# lia.net
KiCad netlist of a schematic drawn in EAGLE
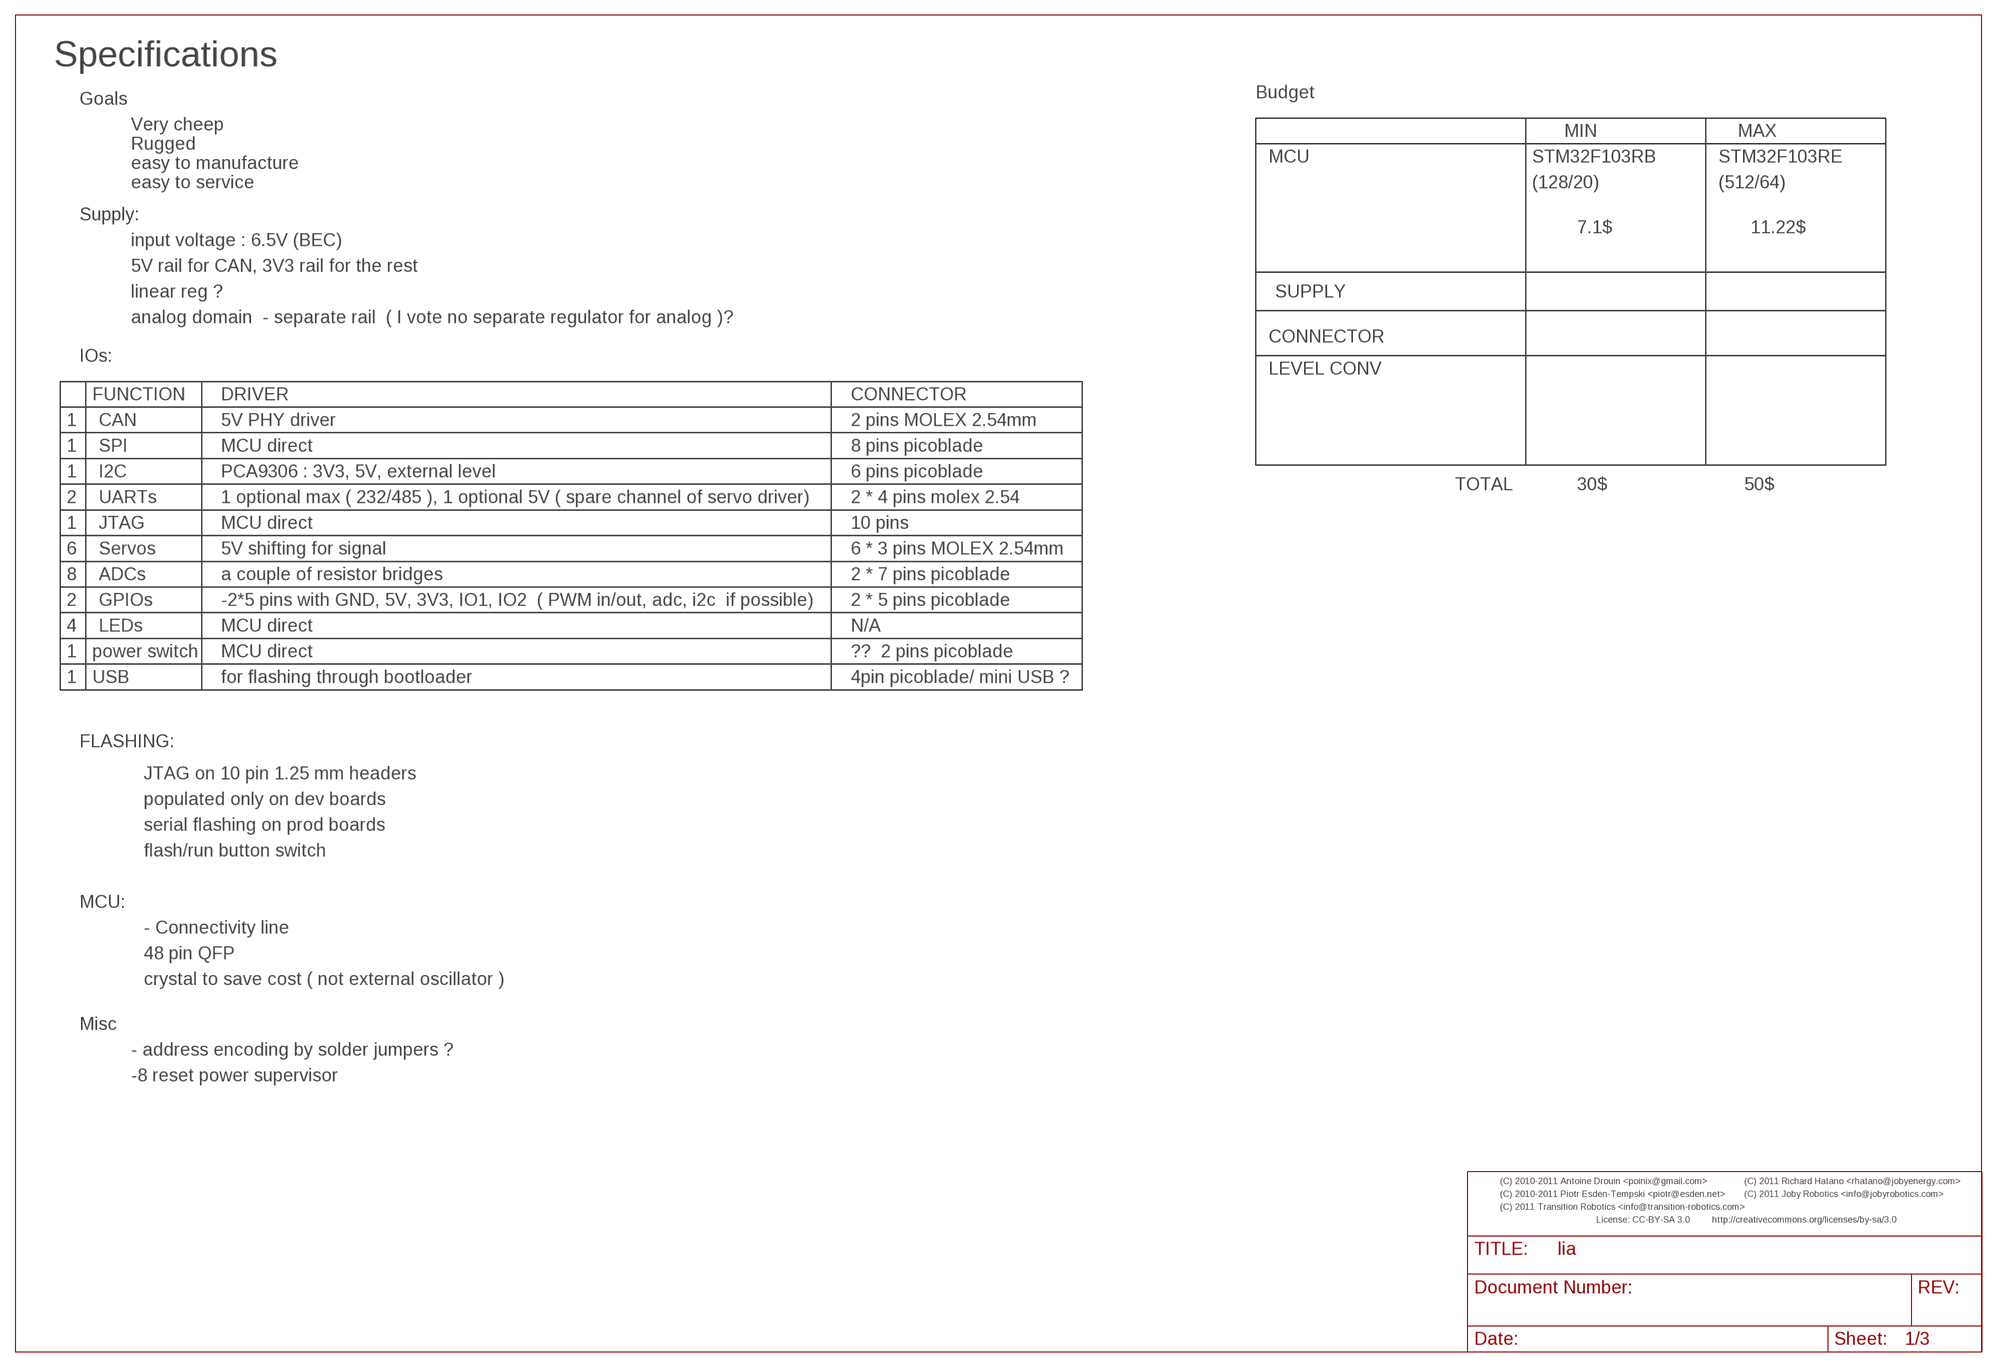
[diagram p0: schematic, sheet 1]
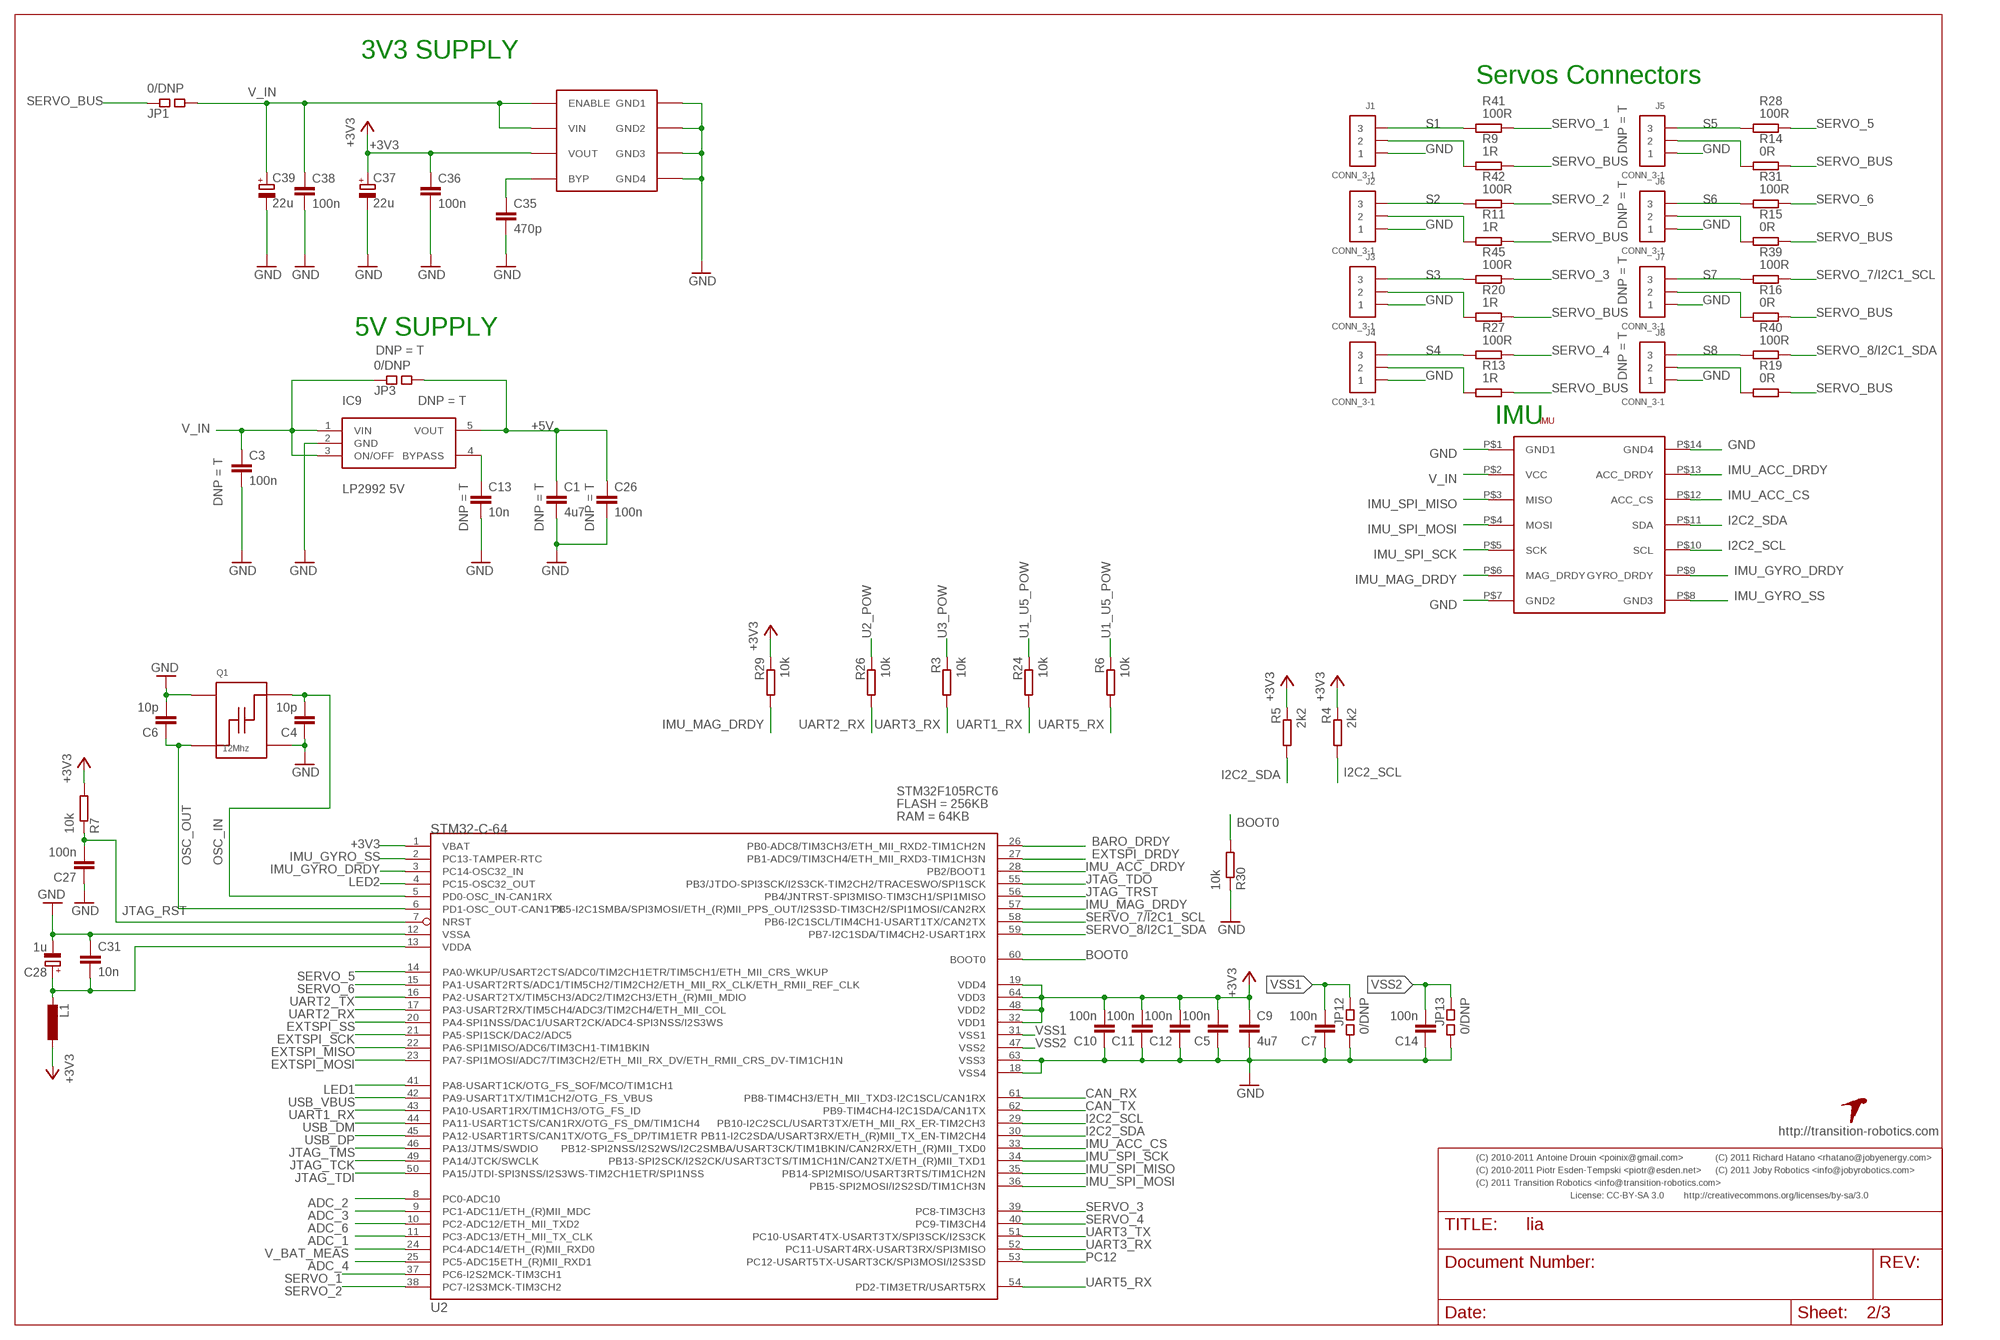
[diagram p1: schematic, sheet 2]
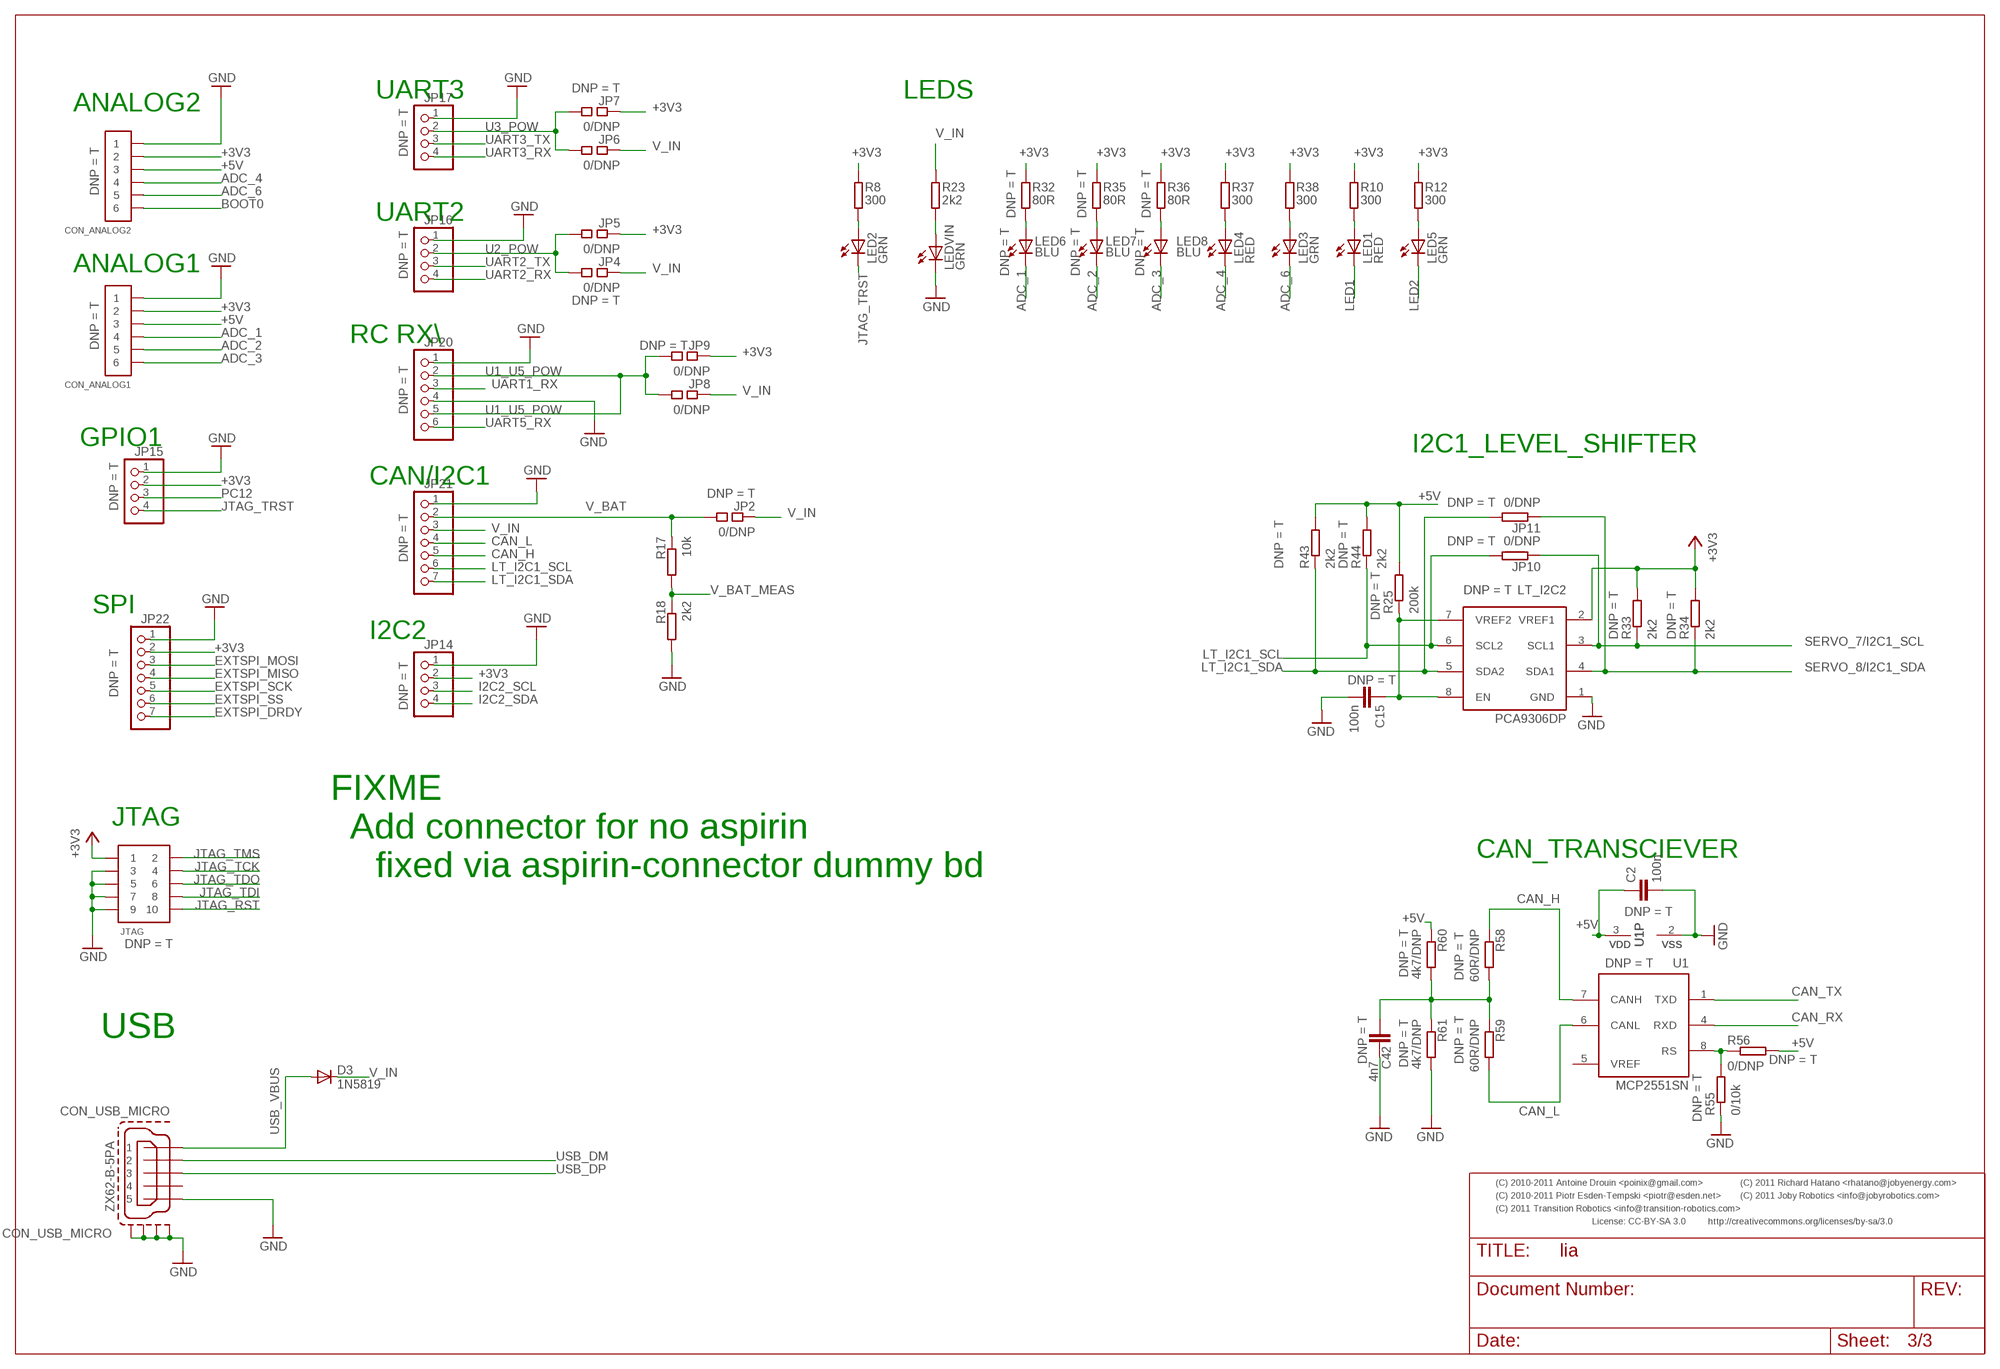
[diagram p2: schematic, sheet 3]

(export (version "E")
  (design (tool "Eeschema 10.0.6"))
  (components
    (comp (ref "C1")
      (value "4u7")
      (footprint "eagle-import:0805-CAP")
      (fields (field (name "DNP") "T") (field (name "PARTNO") "cap-cer-0805-4u7"))
      (libsource (lib "eagle-import") (part "CAPACITOR-0805"))
    )
    (comp (ref "C3")
      (value "100n")
      (footprint "eagle-import:0603-CAP")
      (fields (field (name "DNP") "T") (field (name "PARTNO") "cap-cer-0603-100n"))
      (libsource (lib "eagle-import") (part "CAPACITOR-0603"))
    )
    (comp (ref "C4")
      (value "10p")
      (footprint "eagle-import:0402-CAP")
      (fields (field (name "PARTNO") "cap-cer-0402-10p"))
      (libsource (lib "eagle-import") (part "CAPACITOR-0402"))
    )
    (comp (ref "C5")
      (value "100n")
      (footprint "eagle-import:0402-CAP")
      (fields (field (name "PARTNO") "cap-cer-0402-100n"))
      (libsource (lib "eagle-import") (part "CAPACITOR-0402"))
    )
    (comp (ref "C6")
      (value "10p")
      (footprint "eagle-import:0402-CAP")
      (fields (field (name "PARTNO") "cap-cer-0402-10p"))
      (libsource (lib "eagle-import") (part "CAPACITOR-0402"))
    )
    (comp (ref "C7")
      (value "100n")
      (footprint "eagle-import:0402-CAP")
      (fields (field (name "PARTNO") "cap-cer-0402-100n"))
      (libsource (lib "eagle-import") (part "CAPACITOR-0402"))
    )
    (comp (ref "C9")
      (value "4u7")
      (footprint "eagle-import:0805-CAP")
      (fields (field (name "PARTNO") "cap-cer-0805-4u7"))
      (libsource (lib "eagle-import") (part "CAPACITOR-0805"))
    )
    (comp (ref "C10")
      (value "100n")
      (footprint "eagle-import:0402-CAP")
      (fields (field (name "PARTNO") "cap-cer-0402-100n"))
      (libsource (lib "eagle-import") (part "CAPACITOR-0402"))
    )
    (comp (ref "C11")
      (value "100n")
      (footprint "eagle-import:0402-CAP")
      (fields (field (name "PARTNO") "cap-cer-0402-100n"))
      (libsource (lib "eagle-import") (part "CAPACITOR-0402"))
    )
    (comp (ref "C12")
      (value "100n")
      (footprint "eagle-import:0402-CAP")
      (fields (field (name "PARTNO") "cap-cer-0402-100n"))
      (libsource (lib "eagle-import") (part "CAPACITOR-0402"))
    )
    (comp (ref "C13")
      (value "10n")
      (footprint "eagle-import:0402-CAP")
      (fields (field (name "DNP") "T") (field (name "PARTNO") "cap-cer-0402-10n"))
      (libsource (lib "eagle-import") (part "CAPACITOR-0402"))
    )
    (comp (ref "C14")
      (value "100n")
      (footprint "eagle-import:0402-CAP")
      (fields (field (name "PARTNO") "cap-cer-0402-100n"))
      (libsource (lib "eagle-import") (part "CAPACITOR-0402"))
    )
    (comp (ref "C26")
      (value "100n")
      (footprint "eagle-import:0603-CAP")
      (fields (field (name "DNP") "T") (field (name "PARTNO") "cap-cer-0603-100n"))
      (libsource (lib "eagle-import") (part "CAPACITOR-0603"))
    )
    (comp (ref "C27")
      (value "100n")
      (footprint "eagle-import:0402-CAP")
      (fields (field (name "PARTNO") "cap-cer-0402-100n"))
      (libsource (lib "eagle-import") (part "CAPACITOR-0402"))
    )
    (comp (ref "C28")
      (value "1u")
      (footprint "eagle-import:0603-POL-CAP")
      (fields (field (name "PARTNO") "cap-tan-0603-1u"))
      (libsource (lib "eagle-import") (part "CAPACITOR-POL-0603"))
    )
    (comp (ref "C31")
      (value "10n")
      (footprint "eagle-import:0402-CAP")
      (fields (field (name "PARTNO") "cap-cer-0402-10n"))
      (libsource (lib "eagle-import") (part "CAPACITOR-0402"))
    )
    (comp (ref "C35")
      (value "470p")
      (footprint "eagle-import:0402-CAP")
      (fields (field (name "PARTNO") "cap-cer-0402-470p"))
      (libsource (lib "eagle-import") (part "CAPACITOR-0402"))
    )
    (comp (ref "C36")
      (value "100n")
      (footprint "eagle-import:0603-CAP")
      (fields (field (name "PARTNO") "cap-cer-0603-100n"))
      (libsource (lib "eagle-import") (part "CAPACITOR-0603"))
    )
    (comp (ref "C37")
      (value "22u")
      (footprint "eagle-import:3528_B")
      (fields (field (name "PARTNO") "cap-tan-B-22u-16v"))
      (libsource (lib "eagle-import") (part "CAPACITOR-POLB"))
    )
    (comp (ref "C38")
      (value "100n")
      (footprint "eagle-import:0402-CAP")
      (fields (field (name "PARTNO") "cap-cer-0402-100n"))
      (libsource (lib "eagle-import") (part "CAPACITOR-0402"))
    )
    (comp (ref "C39")
      (value "22u")
      (footprint "eagle-import:3528_B")
      (fields (field (name "PARTNO") "cap-tan-B-22u-16v"))
      (libsource (lib "eagle-import") (part "CAPACITOR-POLB"))
    )
    (comp (ref "IC9")
      (value "LP2992 5V")
      (footprint "eagle-import:SOT23-5")
      (fields (field (name "DNP") "T") (field (name "PARTNO") "vreg-sot-23-5-5v"))
      (libsource (lib "eagle-import") (part "LP2992"))
    )
    (comp (ref "IMU")
      (value "ASPIRIN")
      (footprint "eagle-import:ASPIRIN_1")
      (fields (field (name "PARTNO") "pcb-ass-aspirin"))
      (libsource (lib "eagle-import") (part "ASPIRIN"))
    )
    (comp (ref "J1")
      (value "CONN_3-1")
      (footprint "eagle-import:SIP1X3_100")
      (fields (field (name "PARTNO") "conn-th-0.1in-3-2-ra"))
      (libsource (lib "eagle-import") (part "CONN_3-1"))
    )
    (comp (ref "J2")
      (value "CONN_3-1")
      (footprint "eagle-import:SIP1X3_100")
      (fields (field (name "PARTNO") "conn-th-0.1in-3-2-ra"))
      (libsource (lib "eagle-import") (part "CONN_3-1"))
    )
    (comp (ref "J3")
      (value "CONN_3-1")
      (footprint "eagle-import:SIP1X3_100")
      (fields (field (name "PARTNO") "conn-th-0.1in-3-2-ra"))
      (libsource (lib "eagle-import") (part "CONN_3-1"))
    )
    (comp (ref "J4")
      (value "CONN_3-1")
      (footprint "eagle-import:SIP1X3_100")
      (fields (field (name "PARTNO") "conn-th-0.1in-3-2-ra"))
      (libsource (lib "eagle-import") (part "CONN_3-1"))
    )
    (comp (ref "J5")
      (value "CONN_3-1")
      (footprint "eagle-import:SIP1X3_100")
      (fields (field (name "DNP") "T") (field (name "PARTNO") "conn-th-0.1in-3-2-ra"))
      (libsource (lib "eagle-import") (part "CONN_3-1"))
    )
    (comp (ref "J6")
      (value "CONN_3-1")
      (footprint "eagle-import:SIP1X3_100")
      (fields (field (name "DNP") "T") (field (name "PARTNO") "conn-th-0.1in-3-2-ra"))
      (libsource (lib "eagle-import") (part "CONN_3-1"))
    )
    (comp (ref "J7")
      (value "CONN_3-1")
      (footprint "eagle-import:SIP1X3_100")
      (fields (field (name "DNP") "T") (field (name "PARTNO") "conn-th-0.1in-3-2-ra"))
      (libsource (lib "eagle-import") (part "CONN_3-1"))
    )
    (comp (ref "J8")
      (value "CONN_3-1")
      (footprint "eagle-import:SIP1X3_100")
      (fields (field (name "DNP") "T") (field (name "PARTNO") "conn-th-0.1in-3-2-ra"))
      (libsource (lib "eagle-import") (part "CONN_3-1"))
    )
    (comp (ref "JP1")
      (value "0/DNP")
      (footprint "eagle-import:0402-SQJMP")
      (fields (field (name "PARTNO") "res-0402-0"))
      (libsource (lib "eagle-import") (part "SQ_JMP-0402"))
    )
    (comp (ref "JP3")
      (value "0/DNP")
      (footprint "eagle-import:0402-SQJMP")
      (fields (field (name "DNP") "T") (field (name "PARTNO") "res-0402-0"))
      (libsource (lib "eagle-import") (part "SQ_JMP-0402"))
    )
    (comp (ref "JP12")
      (value "0/DNP")
      (footprint "eagle-import:0402-SQJMP")
      (fields (field (name "PARTNO") "res-0402-0"))
      (libsource (lib "eagle-import") (part "SQ_JMP-0402"))
    )
    (comp (ref "JP13")
      (value "0/DNP")
      (footprint "eagle-import:0402-SQJMP")
      (fields (field (name "PARTNO") "res-0402-0"))
      (libsource (lib "eagle-import") (part "SQ_JMP-0402"))
    )
    (comp (ref "L1")
      (value "INDUCTOR-0603")
      (footprint "eagle-import:0603-IND")
      (fields (field (name "PARTNO") "ferrite-0603-600ohm"))
      (libsource (lib "eagle-import") (part "INDUCTOR-0603"))
    )
    (comp (ref "Q1")
      (value "12Mhz")
      (footprint "eagle-import:ABM8")
      (fields (field (name "PARTNO") "xtal-abm8-12mhz"))
      (libsource (lib "eagle-import") (part "ABM8"))
    )
    (comp (ref "R3")
      (value "10k")
      (footprint "eagle-import:0402-RES")
      (fields (field (name "PARTNO") "res-0402-10k"))
      (libsource (lib "eagle-import") (part "RESISTOR-0402"))
    )
    (comp (ref "R4")
      (value "2k2")
      (footprint "eagle-import:0402-RES")
      (fields (field (name "PARTNO") "res-0402-2k2"))
      (libsource (lib "eagle-import") (part "RESISTOR-0402"))
    )
    (comp (ref "R5")
      (value "2k2")
      (footprint "eagle-import:0402-RES")
      (fields (field (name "PARTNO") "res-0402-2k2"))
      (libsource (lib "eagle-import") (part "RESISTOR-0402"))
    )
    (comp (ref "R6")
      (value "10k")
      (footprint "eagle-import:0402-RES")
      (fields (field (name "PARTNO") "res-0402-10k"))
      (libsource (lib "eagle-import") (part "RESISTOR-0402"))
    )
    (comp (ref "R7")
      (value "10k")
      (footprint "eagle-import:0402-RES")
      (fields (field (name "PARTNO") "res-0402-10k"))
      (libsource (lib "eagle-import") (part "RESISTOR-0402"))
    )
    (comp (ref "R9")
      (value "1R")
      (footprint "eagle-import:1206-RES")
      (fields (field (name "PARTNO") "res-1206-1"))
      (libsource (lib "eagle-import") (part "RESISTOR-1206"))
    )
    (comp (ref "R11")
      (value "1R")
      (footprint "eagle-import:1206-RES")
      (fields (field (name "PARTNO") "res-1206-1"))
      (libsource (lib "eagle-import") (part "RESISTOR-1206"))
    )
    (comp (ref "R13")
      (value "1R")
      (footprint "eagle-import:1206-RES")
      (fields (field (name "PARTNO") "res-1206-1"))
      (libsource (lib "eagle-import") (part "RESISTOR-1206"))
    )
    (comp (ref "R14")
      (value "0R")
      (footprint "eagle-import:1206-RES")
      (fields (field (name "PARTNO") "res-1206-0"))
      (libsource (lib "eagle-import") (part "RESISTOR-1206"))
    )
    (comp (ref "R15")
      (value "0R")
      (footprint "eagle-import:1206-RES")
      (fields (field (name "PARTNO") "res-1206-0"))
      (libsource (lib "eagle-import") (part "RESISTOR-1206"))
    )
    (comp (ref "R16")
      (value "0R")
      (footprint "eagle-import:1206-RES")
      (fields (field (name "PARTNO") "res-1206-0"))
      (libsource (lib "eagle-import") (part "RESISTOR-1206"))
    )
    (comp (ref "R19")
      (value "0R")
      (footprint "eagle-import:1206-RES")
      (fields (field (name "PARTNO") "res-1206-0"))
      (libsource (lib "eagle-import") (part "RESISTOR-1206"))
    )
    (comp (ref "R20")
      (value "1R")
      (footprint "eagle-import:1206-RES")
      (fields (field (name "PARTNO") "res-1206-1"))
      (libsource (lib "eagle-import") (part "RESISTOR-1206"))
    )
    (comp (ref "R24")
      (value "10k")
      (footprint "eagle-import:0402-RES")
      (fields (field (name "PARTNO") "res-0402-10k"))
      (libsource (lib "eagle-import") (part "RESISTOR-0402"))
    )
    (comp (ref "R26")
      (value "10k")
      (footprint "eagle-import:0402-RES")
      (fields (field (name "PARTNO") "res-0402-10k"))
      (libsource (lib "eagle-import") (part "RESISTOR-0402"))
    )
    (comp (ref "R27")
      (value "100R")
      (footprint "eagle-import:0402-RES")
      (fields (field (name "PARTNO") "res-0402-100"))
      (libsource (lib "eagle-import") (part "RESISTOR-0402"))
    )
    (comp (ref "R28")
      (value "100R")
      (footprint "eagle-import:0402-RES")
      (fields (field (name "PARTNO") "res-0402-100"))
      (libsource (lib "eagle-import") (part "RESISTOR-0402"))
    )
    (comp (ref "R29")
      (value "10k")
      (footprint "eagle-import:0402-RES")
      (fields (field (name "PARTNO") "res-0402-10k"))
      (libsource (lib "eagle-import") (part "RESISTOR-0402"))
    )
    (comp (ref "R30")
      (value "10k")
      (footprint "eagle-import:0402-RES")
      (fields (field (name "PARTNO") "res-0402-10k"))
      (libsource (lib "eagle-import") (part "RESISTOR-0402"))
    )
    (comp (ref "R31")
      (value "100R")
      (footprint "eagle-import:0402-RES")
      (fields (field (name "PARTNO") "res-0402-100"))
      (libsource (lib "eagle-import") (part "RESISTOR-0402"))
    )
    (comp (ref "R39")
      (value "100R")
      (footprint "eagle-import:0402-RES")
      (fields (field (name "PARTNO") "res-0402-100"))
      (libsource (lib "eagle-import") (part "RESISTOR-0402"))
    )
    (comp (ref "R40")
      (value "100R")
      (footprint "eagle-import:0402-RES")
      (fields (field (name "PARTNO") "res-0402-100"))
      (libsource (lib "eagle-import") (part "RESISTOR-0402"))
    )
    (comp (ref "R41")
      (value "100R")
      (footprint "eagle-import:0402-RES")
      (fields (field (name "PARTNO") "res-0402-100"))
      (libsource (lib "eagle-import") (part "RESISTOR-0402"))
    )
    (comp (ref "R42")
      (value "100R")
      (footprint "eagle-import:0402-RES")
      (fields (field (name "PARTNO") "res-0402-100"))
      (libsource (lib "eagle-import") (part "RESISTOR-0402"))
    )
    (comp (ref "R45")
      (value "100R")
      (footprint "eagle-import:0402-RES")
      (fields (field (name "PARTNO") "res-0402-100"))
      (libsource (lib "eagle-import") (part "RESISTOR-0402"))
    )
    (comp (ref "U$1")
      (value "TR-LOGO")
      (footprint "eagle-import:TR-LOGO")
      (libsource (lib "eagle-import") (part "TR-LOGO"))
    )
    (comp (ref "U2")
      (value "STM32-C-64")
      (footprint "eagle-import:LQFP64")
      (fields
        (field (name "FLASH") "256KB")
        (field (name "PARTNO") "mcu-lqfp-64-stm32")
        (field (name "PART_NR") "STM32F105RCT6")
        (field (name "RAM") "64KB")
      )
      (libsource (lib "eagle-import") (part "STM32-C-64"))
    )
    (comp (ref "VREG1")
      (value "MIC5209")
      (footprint "eagle-import:SOIC8")
      (fields (field (name "PARTNO") "vreg-so8-3v3"))
      (libsource (lib "eagle-import") (part "MIC5209"))
    )
    (comp (ref "C2")
      (value "100n")
      (footprint "eagle-import:0402-CAP")
      (fields (field (name "DNP") "T") (field (name "PARTNO") "cap-cer-0402-100n"))
      (libsource (lib "eagle-import") (part "CAPACITOR-0402"))
    )
    (comp (ref "C15")
      (value "100n")
      (footprint "eagle-import:0402-CAP")
      (fields (field (name "DNP") "T") (field (name "PARTNO") "cap-cer-0402-100n"))
      (libsource (lib "eagle-import") (part "CAPACITOR-0402"))
    )
    (comp (ref "C42")
      (value "4n7")
      (footprint "eagle-import:0603-CAP")
      (fields (field (name "DNP") "T") (field (name "PARTNO") "cap-cer-0603-4n7"))
      (libsource (lib "eagle-import") (part "CAPACITOR-0603"))
    )
    (comp (ref "CON_ANALOG1")
      (value "CONN_6-1-53398")
      (footprint "eagle-import:PB-53398-06")
      (fields (field (name "DNP") "T") (field (name "PARTNO") "conn-picoblade-smd-0.05in-6-vert"))
      (libsource (lib "eagle-import") (part "CONN_6-1-53398"))
    )
    (comp (ref "CON_ANALOG2")
      (value "CONN_6-1-53398")
      (footprint "eagle-import:PB-53398-06")
      (fields (field (name "DNP") "T") (field (name "PARTNO") "conn-picoblade-smd-0.05in-6-vert"))
      (libsource (lib "eagle-import") (part "CONN_6-1-53398"))
    )
    (comp (ref "CON_USB_MICRO")
      (value "ZX62-B-5PA")
      (footprint "eagle-import:ZX62-B-5PA")
      (fields (field (name "PARTNO") "conn-smd-usb-micro-b"))
      (libsource (lib "eagle-import") (part "ZX62-B-5PA"))
    )
    (comp (ref "D3")
      (value "1N5819")
      (footprint "eagle-import:MICROMELF-R")
      (fields (field (name "PARTNO") "diode-schottky-1608"))
      (libsource (lib "eagle-import") (part "DIODE-MICROMELF-R"))
    )
    (comp (ref "JP2")
      (value "0/DNP")
      (footprint "eagle-import:0402-SQJMP")
      (fields (field (name "DNP") "T") (field (name "PARTNO") "res-0402-0"))
      (libsource (lib "eagle-import") (part "SQ_JMP-0402"))
    )
    (comp (ref "JP4")
      (value "0/DNP")
      (footprint "eagle-import:0402-SQJMP")
      (fields (field (name "DNP") "T") (field (name "PARTNO") "res-0402-0"))
      (libsource (lib "eagle-import") (part "SQ_JMP-0402"))
    )
    (comp (ref "JP5")
      (value "0/DNP")
      (footprint "eagle-import:0402-SQJMP")
      (fields (field (name "PARTNO") "res-0402-0"))
      (libsource (lib "eagle-import") (part "SQ_JMP-0402"))
    )
    (comp (ref "JP6")
      (value "0/DNP")
      (footprint "eagle-import:0402-SQJMP")
      (fields (field (name "PARTNO") "res-0402-0"))
      (libsource (lib "eagle-import") (part "SQ_JMP-0402"))
    )
    (comp (ref "JP7")
      (value "0/DNP")
      (footprint "eagle-import:0402-SQJMP")
      (fields (field (name "DNP") "T") (field (name "PARTNO") "res-0402-0"))
      (libsource (lib "eagle-import") (part "SQ_JMP-0402"))
    )
    (comp (ref "JP8")
      (value "0/DNP")
      (footprint "eagle-import:0402-SQJMP")
      (fields (field (name "PARTNO") "res-0402-0"))
      (libsource (lib "eagle-import") (part "SQ_JMP-0402"))
    )
    (comp (ref "JP9")
      (value "0/DNP")
      (footprint "eagle-import:0402-SQJMP")
      (fields (field (name "DNP") "T") (field (name "PARTNO") "res-0402-0"))
      (libsource (lib "eagle-import") (part "SQ_JMP-0402"))
    )
    (comp (ref "JP10")
      (value "0/DNP")
      (footprint "eagle-import:0603-RES")
      (fields (field (name "DNP") "T") (field (name "PARTNO") "res-0603-0"))
      (libsource (lib "eagle-import") (part "RESISTOR-0603"))
    )
    (comp (ref "JP11")
      (value "0/DNP")
      (footprint "eagle-import:0603-RES")
      (fields (field (name "DNP") "T") (field (name "PARTNO") "res-0603-0"))
      (libsource (lib "eagle-import") (part "RESISTOR-0603"))
    )
    (comp (ref "JP14")
      (value "PINHD-1X4")
      (footprint "eagle-import:1X04")
      (fields (field (name "DNP") "T") (field (name "PARTNO") "conn-th-0.1in-4-1"))
      (libsource (lib "eagle-import") (part "PINHD-1X4"))
    )
    (comp (ref "JP15")
      (value "PINHD-1X4")
      (footprint "eagle-import:1X04")
      (fields (field (name "DNP") "T") (field (name "PARTNO") "conn-th-0.1in-4-1"))
      (libsource (lib "eagle-import") (part "PINHD-1X4"))
    )
    (comp (ref "JP16")
      (value "PINHD-1X4")
      (footprint "eagle-import:1X04")
      (fields (field (name "DNP") "T") (field (name "PARTNO") "conn-th-0.1in-4-1"))
      (libsource (lib "eagle-import") (part "PINHD-1X4"))
    )
    (comp (ref "JP17")
      (value "PINHD-1X4")
      (footprint "eagle-import:1X04")
      (fields (field (name "DNP") "T") (field (name "PARTNO") "conn-th-0.1in-4-1"))
      (libsource (lib "eagle-import") (part "PINHD-1X4"))
    )
    (comp (ref "JP20")
      (value "PINHD-1X6")
      (footprint "eagle-import:1X06")
      (fields (field (name "DNP") "T") (field (name "PARTNO") "conn-th-0.1in-6-1"))
      (libsource (lib "eagle-import") (part "PINHD-1X6"))
    )
    (comp (ref "JP21")
      (value "PINHD-1X7")
      (footprint "eagle-import:1X07")
      (fields (field (name "DNP") "T") (field (name "PARTNO") "conn-th-0.1in-7-1"))
      (libsource (lib "eagle-import") (part "PINHD-1X7"))
    )
    (comp (ref "JP22")
      (value "PINHD-1X7")
      (footprint "eagle-import:1X07")
      (fields (field (name "DNP") "T") (field (name "PARTNO") "conn-th-0.1in-7-1"))
      (libsource (lib "eagle-import") (part "PINHD-1X7"))
    )
    (comp (ref "JTAG")
      (value "PIN_HDR_EDG_1.27MM_5-2")
      (footprint "eagle-import:FTSH-105-DV")
      (fields (field (name "DNP") "T") (field (name "PARTNO") "conn-smd-0.05in-5-2"))
      (libsource (lib "eagle-import") (part "CONN_5-2-FTSH-V"))
    )
    (comp (ref "LED1")
      (value "RED")
      (footprint "eagle-import:0402-LED")
      (fields (field (name "PARTNO") "led-0402-red"))
      (libsource (lib "eagle-import") (part "LED-0402"))
    )
    (comp (ref "LED2")
      (value "GRN")
      (footprint "eagle-import:0402-LED")
      (fields (field (name "PARTNO") "led-0402-green"))
      (libsource (lib "eagle-import") (part "LED-0402"))
    )
    (comp (ref "LED3")
      (value "GRN")
      (footprint "eagle-import:0402-LED")
      (fields (field (name "PARTNO") "led-0402-green"))
      (libsource (lib "eagle-import") (part "LED-0402"))
    )
    (comp (ref "LED4")
      (value "RED")
      (footprint "eagle-import:0402-LED")
      (fields (field (name "PARTNO") "led-0402-red"))
      (libsource (lib "eagle-import") (part "LED-0402"))
    )
    (comp (ref "LED5")
      (value "GRN")
      (footprint "eagle-import:0402-LED")
      (fields (field (name "PARTNO") "led-0402-green"))
      (libsource (lib "eagle-import") (part "LED-0402"))
    )
    (comp (ref "LED6")
      (value "BLU")
      (footprint "eagle-import:0402-LED")
      (fields (field (name "DNP") "T") (field (name "PARTNO") "led-0402-blue"))
      (libsource (lib "eagle-import") (part "LED-0402"))
    )
    (comp (ref "LED7")
      (value "BLU")
      (footprint "eagle-import:0402-LED")
      (fields (field (name "DNP") "T") (field (name "PARTNO") "led-0402-blue"))
      (libsource (lib "eagle-import") (part "LED-0402"))
    )
    (comp (ref "LED8")
      (value "BLU")
      (footprint "eagle-import:0402-LED")
      (fields (field (name "DNP") "T") (field (name "PARTNO") "led-0402-blue"))
      (libsource (lib "eagle-import") (part "LED-0402"))
    )
    (comp (ref "LEDVIN")
      (value "GRN")
      (footprint "eagle-import:0402-LED")
      (fields (field (name "PARTNO") "led-0402-green"))
      (libsource (lib "eagle-import") (part "LED-0402"))
    )
    (comp (ref "LT_I2C2")
      (value "PCA9306DP")
      (footprint "eagle-import:TSSOP_B3")
      (fields (field (name "DNP") "T") (field (name "PARTNO") "ic-tssop8-level-trans"))
      (libsource (lib "eagle-import") (part "PCA9306DP"))
    )
    (comp (ref "R8")
      (value "300")
      (footprint "eagle-import:0402-RES")
      (fields (field (name "PARTNO") "res-0402-300"))
      (libsource (lib "eagle-import") (part "RESISTOR-0402"))
    )
    (comp (ref "R10")
      (value "300")
      (footprint "eagle-import:0402-RES")
      (fields (field (name "PARTNO") "res-0402-300"))
      (libsource (lib "eagle-import") (part "RESISTOR-0402"))
    )
    (comp (ref "R12")
      (value "300")
      (footprint "eagle-import:0402-RES")
      (fields (field (name "PARTNO") "res-0402-300"))
      (libsource (lib "eagle-import") (part "RESISTOR-0402"))
    )
    (comp (ref "R17")
      (value "10k")
      (footprint "eagle-import:0402-RES")
      (fields (field (name "PARTNO") "res-0402-10k"))
      (libsource (lib "eagle-import") (part "RESISTOR-0402"))
    )
    (comp (ref "R18")
      (value "2k2")
      (footprint "eagle-import:0402-RES")
      (fields (field (name "PARTNO") "res-0402-2k2"))
      (libsource (lib "eagle-import") (part "RESISTOR-0402"))
    )
    (comp (ref "R23")
      (value "2k2")
      (footprint "eagle-import:0402-RES")
      (fields (field (name "PARTNO") "res-0402-2k2"))
      (libsource (lib "eagle-import") (part "RESISTOR-0402"))
    )
    (comp (ref "R25")
      (value "200k")
      (footprint "eagle-import:0402-RES")
      (fields (field (name "DNP") "T") (field (name "PARTNO") "res-0402-200k"))
      (libsource (lib "eagle-import") (part "RESISTOR-0402"))
    )
    (comp (ref "R32")
      (value "80R")
      (footprint "eagle-import:0402-RES")
      (fields (field (name "DNP") "T") (field (name "PARTNO") "res-0402-80"))
      (libsource (lib "eagle-import") (part "RESISTOR-0402"))
    )
    (comp (ref "R33")
      (value "2k2")
      (footprint "eagle-import:0402-RES")
      (fields (field (name "DNP") "T") (field (name "PARTNO") "res-0402-2k2"))
      (libsource (lib "eagle-import") (part "RESISTOR-0402"))
    )
    (comp (ref "R34")
      (value "2k2")
      (footprint "eagle-import:0402-RES")
      (fields (field (name "DNP") "T") (field (name "PARTNO") "res-0402-2k2"))
      (libsource (lib "eagle-import") (part "RESISTOR-0402"))
    )
    (comp (ref "R35")
      (value "80R")
      (footprint "eagle-import:0402-RES")
      (fields (field (name "DNP") "T") (field (name "PARTNO") "res-0402-80"))
      (libsource (lib "eagle-import") (part "RESISTOR-0402"))
    )
    (comp (ref "R36")
      (value "80R")
      (footprint "eagle-import:0402-RES")
      (fields (field (name "DNP") "T") (field (name "PARTNO") "res-0402-80"))
      (libsource (lib "eagle-import") (part "RESISTOR-0402"))
    )
    (comp (ref "R37")
      (value "300")
      (footprint "eagle-import:0402-RES")
      (fields (field (name "PARTNO") "res-0402-300"))
      (libsource (lib "eagle-import") (part "RESISTOR-0402"))
    )
    (comp (ref "R38")
      (value "300")
      (footprint "eagle-import:0402-RES")
      (fields (field (name "PARTNO") "res-0402-300"))
      (libsource (lib "eagle-import") (part "RESISTOR-0402"))
    )
    (comp (ref "R43")
      (value "2k2")
      (footprint "eagle-import:0402-RES")
      (fields (field (name "DNP") "T") (field (name "PARTNO") "res-0402-1k5"))
      (libsource (lib "eagle-import") (part "RESISTOR-0402"))
    )
    (comp (ref "R44")
      (value "2k2")
      (footprint "eagle-import:0402-RES")
      (fields (field (name "DNP") "T") (field (name "PARTNO") "res-0402-1k5"))
      (libsource (lib "eagle-import") (part "RESISTOR-0402"))
    )
    (comp (ref "R55")
      (value "0/10k")
      (footprint "eagle-import:0402-RES")
      (fields (field (name "DNP") "T") (field (name "PARTNO") "res-0402-10k"))
      (libsource (lib "eagle-import") (part "RESISTOR-0402"))
    )
    (comp (ref "R56")
      (value "0/DNP")
      (footprint "eagle-import:0402-RES")
      (fields (field (name "DNP") "T") (field (name "PARTNO") "res-0402-0"))
      (libsource (lib "eagle-import") (part "RESISTOR-0402"))
    )
    (comp (ref "R58")
      (value "60R/DNP")
      (footprint "eagle-import:0402-RES")
      (fields (field (name "DNP") "T") (field (name "PARTNO") "res-0402-60.4"))
      (libsource (lib "eagle-import") (part "RESISTOR-0402"))
    )
    (comp (ref "R59")
      (value "60R/DNP")
      (footprint "eagle-import:0402-RES")
      (fields (field (name "DNP") "T") (field (name "PARTNO") "res-0402-60.4"))
      (libsource (lib "eagle-import") (part "RESISTOR-0402"))
    )
    (comp (ref "R60")
      (value "4k7/DNP")
      (footprint "eagle-import:0402-RES")
      (fields (field (name "DNP") "T") (field (name "PARTNO") "res-0402-4k7"))
      (libsource (lib "eagle-import") (part "RESISTOR-0402"))
    )
    (comp (ref "R61")
      (value "4k7/DNP")
      (footprint "eagle-import:0402-RES")
      (fields (field (name "DNP") "T") (field (name "PARTNO") "res-0402-4k7"))
      (libsource (lib "eagle-import") (part "RESISTOR-0402"))
    )
    (comp (ref "U1")
      (value "MCP2551SN")
      (footprint "eagle-import:SO-08")
      (fields (field (name "DNP") "T") (field (name "PARTNO") "ic-so8-can"))
      (libsource (lib "eagle-import") (part "MCP2551SN"))
    )
  )
  (nets
    (net (code "1") (name "+3V3") (class "Default")
      (node (ref "C10") (pin "P$2") (pinfunction "2_P$2") (pintype "passive"))
      (node (ref "C11") (pin "P$2") (pinfunction "2_P$2") (pintype "passive"))
      (node (ref "C12") (pin "P$2") (pinfunction "2_P$2") (pintype "passive"))
      (node (ref "C36") (pin "P$1") (pinfunction "1_P$1") (pintype "passive"))
      (node (ref "C37") (pin "+") (pinfunction "+_+") (pintype "passive"))
      (node (ref "C5") (pin "P$2") (pinfunction "2_P$2") (pintype "passive"))
      (node (ref "C9") (pin "P$1") (pinfunction "1_P$1") (pintype "passive"))
      (node (ref "CON_ANALOG1") (pin "2") (pinfunction "2_2") (pintype "bidirectional"))
      (node (ref "CON_ANALOG2") (pin "2") (pinfunction "2_2") (pintype "bidirectional"))
      (node (ref "JP14") (pin "2") (pinfunction "2_2") (pintype "passive"))
      (node (ref "JP15") (pin "2") (pinfunction "2_2") (pintype "passive"))
      (node (ref "JP22") (pin "2") (pinfunction "2_2") (pintype "passive"))
      (node (ref "JP5") (pin "P$1") (pinfunction "1_P$1") (pintype "passive"))
      (node (ref "JP7") (pin "P$1") (pinfunction "1_P$1") (pintype "passive"))
      (node (ref "JP9") (pin "P$1") (pinfunction "1_P$1") (pintype "passive"))
      (node (ref "JTAG") (pin "1") (pinfunction "1_1") (pintype "bidirectional"))
      (node (ref "L1") (pin "P$1") (pinfunction "1_P$1") (pintype "passive"))
      (node (ref "LT_I2C2") (pin "2") (pinfunction "VREF1_2") (pintype "bidirectional"))
      (node (ref "R10") (pin "P$2") (pinfunction "2_P$2") (pintype "passive"))
      (node (ref "R12") (pin "P$2") (pinfunction "2_P$2") (pintype "passive"))
      (node (ref "R29") (pin "P$1") (pinfunction "1_P$1") (pintype "passive"))
      (node (ref "R32") (pin "P$2") (pinfunction "2_P$2") (pintype "passive"))
      (node (ref "R33") (pin "P$2") (pinfunction "2_P$2") (pintype "passive"))
      (node (ref "R34") (pin "P$2") (pinfunction "2_P$2") (pintype "passive"))
      (node (ref "R35") (pin "P$2") (pinfunction "2_P$2") (pintype "passive"))
      (node (ref "R36") (pin "P$2") (pinfunction "2_P$2") (pintype "passive"))
      (node (ref "R37") (pin "P$2") (pinfunction "2_P$2") (pintype "passive"))
      (node (ref "R38") (pin "P$2") (pinfunction "2_P$2") (pintype "passive"))
      (node (ref "R4") (pin "P$1") (pinfunction "1_P$1") (pintype "passive"))
      (node (ref "R5") (pin "P$1") (pinfunction "1_P$1") (pintype "passive"))
      (node (ref "R7") (pin "P$2") (pinfunction "2_P$2") (pintype "passive"))
      (node (ref "R8") (pin "P$2") (pinfunction "2_P$2") (pintype "passive"))
      (node (ref "U2") (pin "1") (pinfunction "VBAT_1") (pintype "power_in"))
      (node (ref "U2") (pin "19") (pinfunction "VDD4_19") (pintype "bidirectional"))
      (node (ref "U2") (pin "32") (pinfunction "VDD1_32") (pintype "power_in"))
      (node (ref "U2") (pin "48") (pinfunction "VDD2_48") (pintype "power_in"))
      (node (ref "U2") (pin "64") (pinfunction "VDD3_64") (pintype "power_in"))
      (node (ref "VREG1") (pin "3") (pinfunction "VOUT_3") (pintype "bidirectional"))
    )
    (net (code "2") (name "+5V") (class "Default")
      (node (ref "C1") (pin "P$1") (pinfunction "1_P$1") (pintype "passive"))
      (node (ref "C2") (pin "P$1") (pinfunction "1_P$1") (pintype "passive"))
      (node (ref "C26") (pin "P$1") (pinfunction "1_P$1") (pintype "passive"))
      (node (ref "CON_ANALOG1") (pin "3") (pinfunction "3_3") (pintype "bidirectional"))
      (node (ref "CON_ANALOG2") (pin "3") (pinfunction "3_3") (pintype "bidirectional"))
      (node (ref "IC9") (pin "5") (pinfunction "VOUT_5") (pintype "bidirectional"))
      (node (ref "JP3") (pin "P$2") (pinfunction "2_P$2") (pintype "passive"))
      (node (ref "R25") (pin "P$2") (pinfunction "2_P$2") (pintype "passive"))
      (node (ref "R43") (pin "P$2") (pinfunction "2_P$2") (pintype "passive"))
      (node (ref "R44") (pin "P$2") (pinfunction "2_P$2") (pintype "passive"))
      (node (ref "R56") (pin "P$2") (pinfunction "2_P$2") (pintype "passive"))
      (node (ref "R60") (pin "P$1") (pinfunction "1_P$1") (pintype "passive"))
      (node (ref "U1") (pin "3") (pinfunction "VDD_3") (pintype "power_in"))
    )
    (net (code "3") (name "ADC_1") (class "Default")
      (node (ref "CON_ANALOG1") (pin "4") (pinfunction "4_4") (pintype "bidirectional"))
      (node (ref "LED6") (pin "C") (pinfunction "C_C") (pintype "passive"))
      (node (ref "U2") (pin "11") (pinfunction "PC3-ADC13/ETH_MII_TX_CLK_11") (pintype "bidirectional"))
    )
    (net (code "4") (name "ADC_2") (class "Default")
      (node (ref "CON_ANALOG1") (pin "5") (pinfunction "5_5") (pintype "bidirectional"))
      (node (ref "LED7") (pin "C") (pinfunction "C_C") (pintype "passive"))
      (node (ref "U2") (pin "8") (pinfunction "PC0-ADC10_8") (pintype "bidirectional"))
    )
    (net (code "5") (name "ADC_3") (class "Default")
      (node (ref "CON_ANALOG1") (pin "6") (pinfunction "6_6") (pintype "bidirectional"))
      (node (ref "LED8") (pin "C") (pinfunction "C_C") (pintype "passive"))
      (node (ref "U2") (pin "9") (pinfunction "PC1-ADC11/ETH_(R)MII_MDC_9") (pintype "bidirectional"))
    )
    (net (code "6") (name "ADC_4") (class "Default")
      (node (ref "CON_ANALOG2") (pin "4") (pinfunction "4_4") (pintype "bidirectional"))
      (node (ref "LED4") (pin "C") (pinfunction "C_C") (pintype "passive"))
      (node (ref "U2") (pin "25") (pinfunction "PC5-ADC15ETH_(R)MII_RXD1_25") (pintype "bidirectional"))
    )
    (net (code "7") (name "ADC_6") (class "Default")
      (node (ref "CON_ANALOG2") (pin "5") (pinfunction "5_5") (pintype "bidirectional"))
      (node (ref "LED3") (pin "C") (pinfunction "C_C") (pintype "passive"))
      (node (ref "U2") (pin "10") (pinfunction "PC2-ADC12/ETH_MII_TXD2_10") (pintype "bidirectional"))
    )
    (net (code "8") (name "BARO_DRDY") (class "Default")
      (node (ref "U2") (pin "26") (pinfunction "PB0-ADC8/TIM3CH3/ETH_MII_RXD2-TIM1CH2N_26") (pintype "bidirectional"))
    )
    (net (code "9") (name "BOOT0") (class "Default")
      (node (ref "CON_ANALOG2") (pin "6") (pinfunction "6_6") (pintype "bidirectional"))
      (node (ref "R30") (pin "P$2") (pinfunction "2_P$2") (pintype "passive"))
      (node (ref "U2") (pin "60") (pinfunction "BOOT0_60") (pintype "input"))
    )
    (net (code "10") (name "CAN_H") (class "Default")
      (node (ref "JP21") (pin "5") (pinfunction "5_5") (pintype "passive"))
      (node (ref "R58") (pin "P$1") (pinfunction "1_P$1") (pintype "passive"))
      (node (ref "U1") (pin "7") (pinfunction "CANH_7") (pintype "bidirectional"))
    )
    (net (code "11") (name "CAN_L") (class "Default")
      (node (ref "JP21") (pin "4") (pinfunction "4_4") (pintype "passive"))
      (node (ref "R59") (pin "P$2") (pinfunction "2_P$2") (pintype "passive"))
      (node (ref "U1") (pin "6") (pinfunction "CANL_6") (pintype "bidirectional"))
    )
    (net (code "12") (name "CAN_RX") (class "Default")
      (node (ref "U1") (pin "4") (pinfunction "RXD_4") (pintype "output"))
      (node (ref "U2") (pin "61") (pinfunction "PB8-TIM4CH3/ETH_MII_TXD3-I2C1SCL/CAN1RX_61") (pintype "bidirectional"))
    )
    (net (code "13") (name "CAN_TX") (class "Default")
      (node (ref "U1") (pin "1") (pinfunction "TXD_1") (pintype "input"))
      (node (ref "U2") (pin "62") (pinfunction "PB9-TIM4CH4-I2C1SDA/CAN1TX_62") (pintype "bidirectional"))
    )
    (net (code "14") (name "EXTSPI_DRDY") (class "Default")
      (node (ref "JP22") (pin "7") (pinfunction "7_7") (pintype "passive"))
      (node (ref "U2") (pin "27") (pinfunction "PB1-ADC9/TIM3CH4/ETH_MII_RXD3-TIM1CH3N_27") (pintype "bidirectional"))
    )
    (net (code "15") (name "EXTSPI_MISO") (class "Default")
      (node (ref "JP22") (pin "4") (pinfunction "4_4") (pintype "passive"))
      (node (ref "U2") (pin "22") (pinfunction "PA6-SPI1MISO/ADC6/TIM3CH1-TIM1BKIN_22") (pintype "bidirectional"))
    )
    (net (code "16") (name "EXTSPI_MOSI") (class "Default")
      (node (ref "JP22") (pin "3") (pinfunction "3_3") (pintype "passive"))
      (node (ref "U2") (pin "23") (pinfunction "PA7-SPI1MOSI/ADC7/TIM3CH2/ETH_MII_RX_DV/ETH_RMII_CRS_DV-TIM1CH1N_23") (pintype "bidirectional"))
    )
    (net (code "17") (name "EXTSPI_SCK") (class "Default")
      (node (ref "JP22") (pin "5") (pinfunction "5_5") (pintype "passive"))
      (node (ref "U2") (pin "21") (pinfunction "PA5-SPI1SCK/DAC2/ADC5_21") (pintype "bidirectional"))
    )
    (net (code "18") (name "EXTSPI_SS") (class "Default")
      (node (ref "JP22") (pin "6") (pinfunction "6_6") (pintype "passive"))
      (node (ref "U2") (pin "20") (pinfunction "PA4-SPI1NSS/DAC1/USART2CK/ADC4-SPI3NSS/I2S3WS_20") (pintype "bidirectional"))
    )
    (net (code "19") (name "GND") (class "Default")
      (node (ref "C1") (pin "P$2") (pinfunction "2_P$2") (pintype "passive"))
      (node (ref "C10") (pin "P$1") (pinfunction "1_P$1") (pintype "passive"))
      (node (ref "C11") (pin "P$1") (pinfunction "1_P$1") (pintype "passive"))
      (node (ref "C12") (pin "P$1") (pinfunction "1_P$1") (pintype "passive"))
      (node (ref "C13") (pin "P$2") (pinfunction "2_P$2") (pintype "passive"))
      (node (ref "C14") (pin "P$1") (pinfunction "1_P$1") (pintype "passive"))
      (node (ref "C15") (pin "P$2") (pinfunction "2_P$2") (pintype "passive"))
      (node (ref "C2") (pin "P$2") (pinfunction "2_P$2") (pintype "passive"))
      (node (ref "C26") (pin "P$2") (pinfunction "2_P$2") (pintype "passive"))
      (node (ref "C27") (pin "P$1") (pinfunction "1_P$1") (pintype "passive"))
      (node (ref "C28") (pin "-") (pinfunction "-_-") (pintype "passive"))
      (node (ref "C3") (pin "P$2") (pinfunction "2_P$2") (pintype "passive"))
      (node (ref "C31") (pin "P$1") (pinfunction "1_P$1") (pintype "passive"))
      (node (ref "C35") (pin "P$2") (pinfunction "2_P$2") (pintype "passive"))
      (node (ref "C36") (pin "P$2") (pinfunction "2_P$2") (pintype "passive"))
      (node (ref "C37") (pin "-") (pinfunction "-_-") (pintype "passive"))
      (node (ref "C38") (pin "P$2") (pinfunction "2_P$2") (pintype "passive"))
      (node (ref "C39") (pin "-") (pinfunction "-_-") (pintype "passive"))
      (node (ref "C4") (pin "P$1") (pinfunction "1_P$1") (pintype "passive"))
      (node (ref "C42") (pin "P$1") (pinfunction "1_P$1") (pintype "passive"))
      (node (ref "C5") (pin "P$1") (pinfunction "1_P$1") (pintype "passive"))
      (node (ref "C6") (pin "P$2") (pinfunction "2_P$2") (pintype "passive"))
      (node (ref "C7") (pin "P$1") (pinfunction "1_P$1") (pintype "passive"))
      (node (ref "C9") (pin "P$2") (pinfunction "2_P$2") (pintype "passive"))
      (node (ref "CON_ANALOG1") (pin "1") (pinfunction "1_1") (pintype "bidirectional"))
      (node (ref "CON_ANALOG2") (pin "1") (pinfunction "1_1") (pintype "bidirectional"))
      (node (ref "CON_USB_MICRO") (pin "GND_LEFT") (pinfunction "S1_GND_LEFT") (pintype "passive"))
      (node (ref "CON_USB_MICRO") (pin "GND_RIGHT") (pinfunction "S2_GND_RIGHT") (pintype "passive"))
      (node (ref "CON_USB_MICRO") (pin "GND_UP_LEFT") (pinfunction "S3_GND_UP_LEFT") (pintype "passive"))
      (node (ref "CON_USB_MICRO") (pin "GND_UP_RIGHT") (pinfunction "S4_GND_UP_RIGHT") (pintype "passive"))
      (node (ref "CON_USB_MICRO") (pin "PIN_5") (pinfunction "5_PIN_5") (pintype "input"))
      (node (ref "IC9") (pin "2") (pinfunction "GND_2") (pintype "bidirectional"))
      (node (ref "IMU") (pin "P$1") (pinfunction "GND1_P$1") (pintype "bidirectional"))
      (node (ref "IMU") (pin "P$14") (pinfunction "GND4_P$14") (pintype "bidirectional"))
      (node (ref "IMU") (pin "P$7") (pinfunction "GND2_P$7") (pintype "bidirectional"))
      (node (ref "J1") (pin "1") (pinfunction "1_1") (pintype "bidirectional"))
      (node (ref "J2") (pin "1") (pinfunction "1_1") (pintype "bidirectional"))
      (node (ref "J3") (pin "1") (pinfunction "1_1") (pintype "bidirectional"))
      (node (ref "J4") (pin "1") (pinfunction "1_1") (pintype "bidirectional"))
      (node (ref "J5") (pin "1") (pinfunction "1_1") (pintype "bidirectional"))
      (node (ref "J6") (pin "1") (pinfunction "1_1") (pintype "bidirectional"))
      (node (ref "J7") (pin "1") (pinfunction "1_1") (pintype "bidirectional"))
      (node (ref "J8") (pin "1") (pinfunction "1_1") (pintype "bidirectional"))
      (node (ref "JP12") (pin "P$2") (pinfunction "2_P$2") (pintype "passive"))
      (node (ref "JP13") (pin "P$2") (pinfunction "2_P$2") (pintype "passive"))
      (node (ref "JP14") (pin "1") (pinfunction "1_1") (pintype "passive"))
      (node (ref "JP15") (pin "1") (pinfunction "1_1") (pintype "passive"))
      (node (ref "JP16") (pin "1") (pinfunction "1_1") (pintype "passive"))
      (node (ref "JP17") (pin "1") (pinfunction "1_1") (pintype "passive"))
      (node (ref "JP20") (pin "1") (pinfunction "1_1") (pintype "passive"))
      (node (ref "JP20") (pin "4") (pinfunction "4_4") (pintype "passive"))
      (node (ref "JP21") (pin "1") (pinfunction "1_1") (pintype "passive"))
      (node (ref "JP22") (pin "1") (pinfunction "1_1") (pintype "passive"))
      (node (ref "JTAG") (pin "3") (pinfunction "3_3") (pintype "bidirectional"))
      (node (ref "JTAG") (pin "5") (pinfunction "5_5") (pintype "bidirectional"))
      (node (ref "JTAG") (pin "7") (pinfunction "7_7") (pintype "bidirectional"))
      (node (ref "JTAG") (pin "9") (pinfunction "9_9") (pintype "bidirectional"))
      (node (ref "LEDVIN") (pin "C") (pinfunction "C_C") (pintype "passive"))
      (node (ref "LT_I2C2") (pin "1") (pinfunction "GND_1") (pintype "bidirectional"))
      (node (ref "Q1") (pin "P$2") (pinfunction "P$2_P$2") (pintype "bidirectional"))
      (node (ref "Q1") (pin "P$4") (pinfunction "P$4_P$4") (pintype "bidirectional"))
      (node (ref "R18") (pin "P$2") (pinfunction "2_P$2") (pintype "passive"))
      (node (ref "R30") (pin "P$1") (pinfunction "1_P$1") (pintype "passive"))
      (node (ref "R55") (pin "P$1") (pinfunction "1_P$1") (pintype "passive"))
      (node (ref "R61") (pin "P$2") (pinfunction "2_P$2") (pintype "passive"))
      (node (ref "U1") (pin "2") (pinfunction "VSS_2") (pintype "power_in"))
      (node (ref "U2") (pin "12") (pinfunction "VSSA_12") (pintype "power_in"))
      (node (ref "U2") (pin "18") (pinfunction "VSS4_18") (pintype "bidirectional"))
      (node (ref "U2") (pin "63") (pinfunction "VSS3_63") (pintype "power_in"))
      (node (ref "VREG1") (pin "5") (pinfunction "GND4_5") (pintype "bidirectional"))
      (node (ref "VREG1") (pin "6") (pinfunction "GND3_6") (pintype "bidirectional"))
      (node (ref "VREG1") (pin "7") (pinfunction "GND2_7") (pintype "bidirectional"))
      (node (ref "VREG1") (pin "8") (pinfunction "GND1_8") (pintype "bidirectional"))
    )
    (net (code "20") (name "I2C2_SCL") (class "Default")
      (node (ref "IMU") (pin "P$10") (pinfunction "SCL_P$10") (pintype "bidirectional"))
      (node (ref "JP14") (pin "3") (pinfunction "3_3") (pintype "passive"))
      (node (ref "R4") (pin "P$2") (pinfunction "2_P$2") (pintype "passive"))
      (node (ref "U2") (pin "29") (pinfunction "PB10-I2C2SCL/USART3TX/ETH_MII_RX_ER-TIM2CH3_29") (pintype "bidirectional"))
    )
    (net (code "21") (name "I2C2_SDA") (class "Default")
      (node (ref "IMU") (pin "P$11") (pinfunction "SDA_P$11") (pintype "bidirectional"))
      (node (ref "JP14") (pin "4") (pinfunction "4_4") (pintype "passive"))
      (node (ref "R5") (pin "P$2") (pinfunction "2_P$2") (pintype "passive"))
      (node (ref "U2") (pin "30") (pinfunction "PB11-I2C2SDA/USART3RX/ETH_(R)MII_TX_EN-TIM2CH4_30") (pintype "bidirectional"))
    )
    (net (code "22") (name "IMU_ACC_CS") (class "Default")
      (node (ref "IMU") (pin "P$12") (pinfunction "ACC_CS_P$12") (pintype "bidirectional"))
      (node (ref "U2") (pin "33") (pinfunction "PB12-SPI2NSS/I2S2WS/I2C2SMBA/USART3CK/TIM1BKIN/CAN2RX/ETH_(R)MII_TXD0_33") (pintype "bidirectional"))
    )
    (net (code "23") (name "IMU_ACC_DRDY") (class "Default")
      (node (ref "IMU") (pin "P$13") (pinfunction "ACC_DRDY_P$13") (pintype "bidirectional"))
      (node (ref "U2") (pin "28") (pinfunction "PB2/BOOT1_28") (pintype "bidirectional"))
    )
    (net (code "24") (name "IMU_GYRO_DRDY") (class "Default")
      (node (ref "IMU") (pin "P$9") (pinfunction "GYRO_DRDY_P$9") (pintype "bidirectional"))
      (node (ref "U2") (pin "3") (pinfunction "PC14-OSC32_IN_3") (pintype "bidirectional"))
    )
    (net (code "25") (name "IMU_GYRO_SS") (class "Default")
      (node (ref "IMU") (pin "P$8") (pinfunction "GND3_P$8") (pintype "bidirectional"))
      (node (ref "U2") (pin "2") (pinfunction "PC13-TAMPER-RTC_2") (pintype "bidirectional"))
    )
    (net (code "26") (name "IMU_MAG_DRDY") (class "Default")
      (node (ref "IMU") (pin "P$6") (pinfunction "MAG_DRDY_P$6") (pintype "bidirectional"))
      (node (ref "R29") (pin "P$2") (pinfunction "2_P$2") (pintype "passive"))
      (node (ref "U2") (pin "57") (pinfunction "PB5-I2C1SMBA/SPI3MOSI/ETH_(R)MII_PPS_OUT/I2S3SD-TIM3CH2/SPI1MOSI/CAN2RX_57") (pintype "bidirectional"))
    )
    (net (code "27") (name "IMU_SPI_MISO") (class "Default")
      (node (ref "IMU") (pin "P$3") (pinfunction "MISO_P$3") (pintype "bidirectional"))
      (node (ref "U2") (pin "35") (pinfunction "PB14-SPI2MISO/USART3RTS/TIM1CH2N_35") (pintype "bidirectional"))
    )
    (net (code "28") (name "IMU_SPI_MOSI") (class "Default")
      (node (ref "IMU") (pin "P$4") (pinfunction "MOSI_P$4") (pintype "bidirectional"))
      (node (ref "U2") (pin "36") (pinfunction "PB15-SPI2MOSI/I2S2SD/TIM1CH3N_36") (pintype "bidirectional"))
    )
    (net (code "29") (name "IMU_SPI_SCK") (class "Default")
      (node (ref "IMU") (pin "P$5") (pinfunction "SCK_P$5") (pintype "bidirectional"))
      (node (ref "U2") (pin "34") (pinfunction "PB13-SPI2SCK/I2S2CK/USART3CTS/TIM1CH1N/CAN2TX/ETH_(R)MII_TXD1_34") (pintype "bidirectional"))
    )
    (net (code "30") (name "JTAG_RST") (class "Default")
      (node (ref "C27") (pin "P$2") (pinfunction "2_P$2") (pintype "passive"))
      (node (ref "JTAG") (pin "10") (pinfunction "10_10") (pintype "bidirectional"))
      (node (ref "R7") (pin "P$1") (pinfunction "1_P$1") (pintype "passive"))
      (node (ref "U2") (pin "7") (pinfunction "NRST_7") (pintype "bidirectional"))
    )
    (net (code "31") (name "JTAG_TCK") (class "Default")
      (node (ref "JTAG") (pin "4") (pinfunction "4_4") (pintype "bidirectional"))
      (node (ref "U2") (pin "49") (pinfunction "PA14/JTCK/SWCLK_49") (pintype "bidirectional"))
    )
    (net (code "32") (name "JTAG_TDI") (class "Default")
      (node (ref "JTAG") (pin "8") (pinfunction "8_8") (pintype "bidirectional"))
      (node (ref "U2") (pin "50") (pinfunction "PA15/JTDI-SPI3NSS/I2S3WS-TIM2CH1ETR/SPI1NSS_50") (pintype "bidirectional"))
    )
    (net (code "33") (name "JTAG_TDO") (class "Default")
      (node (ref "JTAG") (pin "6") (pinfunction "6_6") (pintype "bidirectional"))
      (node (ref "U2") (pin "55") (pinfunction "PB3/JTDO-SPI3SCK/I2S3CK-TIM2CH2/TRACESWO/SPI1SCK_55") (pintype "bidirectional"))
    )
    (net (code "34") (name "JTAG_TMS") (class "Default")
      (node (ref "JTAG") (pin "2") (pinfunction "2_2") (pintype "bidirectional"))
      (node (ref "U2") (pin "46") (pinfunction "PA13/JTMS/SWDIO_46") (pintype "bidirectional"))
    )
    (net (code "35") (name "JTAG_TRST") (class "Default")
      (node (ref "JP15") (pin "4") (pinfunction "4_4") (pintype "passive"))
      (node (ref "LED2") (pin "C") (pinfunction "C_C") (pintype "passive"))
      (node (ref "U2") (pin "56") (pinfunction "PB4/JNTRST-SPI3MISO-TIM3CH1/SPI1MISO_56") (pintype "bidirectional"))
    )
    (net (code "36") (name "LED1") (class "Default")
      (node (ref "LED1") (pin "C") (pinfunction "C_C") (pintype "passive"))
      (node (ref "U2") (pin "41") (pinfunction "PA8-USART1CK/OTG_FS_SOF/MCO/TIM1CH1_41") (pintype "bidirectional"))
    )
    (net (code "37") (name "LED2") (class "Default")
      (node (ref "LED5") (pin "C") (pinfunction "C_C") (pintype "passive"))
      (node (ref "U2") (pin "4") (pinfunction "PC15-OSC32_OUT_4") (pintype "bidirectional"))
    )
    (net (code "38") (name "LT_I2C1_SCL") (class "Default")
      (node (ref "JP10") (pin "P$2") (pinfunction "2_P$2") (pintype "passive"))
      (node (ref "JP21") (pin "6") (pinfunction "6_6") (pintype "passive"))
      (node (ref "LT_I2C2") (pin "6") (pinfunction "SCL2_6") (pintype "bidirectional"))
      (node (ref "R44") (pin "P$1") (pinfunction "1_P$1") (pintype "passive"))
    )
    (net (code "39") (name "LT_I2C1_SDA") (class "Default")
      (node (ref "JP11") (pin "P$2") (pinfunction "2_P$2") (pintype "passive"))
      (node (ref "JP21") (pin "7") (pinfunction "7_7") (pintype "passive"))
      (node (ref "LT_I2C2") (pin "5") (pinfunction "SDA2_5") (pintype "bidirectional"))
      (node (ref "R43") (pin "P$1") (pinfunction "1_P$1") (pintype "passive"))
    )
    (net (code "40") (name "Net-(C13-1)") (class "Default")
      (node (ref "C13") (pin "P$1") (pinfunction "1_P$1") (pintype "passive"))
      (node (ref "IC9") (pin "4") (pinfunction "BYPASS_4") (pintype "bidirectional"))
    )
    (net (code "41") (name "Net-(C15-1)") (class "Default")
      (node (ref "C15") (pin "P$1") (pinfunction "1_P$1") (pintype "passive"))
      (node (ref "LT_I2C2") (pin "7") (pinfunction "VREF2_7") (pintype "bidirectional"))
      (node (ref "LT_I2C2") (pin "8") (pinfunction "EN_8") (pintype "bidirectional"))
      (node (ref "R25") (pin "P$1") (pinfunction "1_P$1") (pintype "passive"))
    )
    (net (code "42") (name "Net-(C31-2)") (class "Default")
      (node (ref "C28") (pin "+") (pinfunction "+_+") (pintype "passive"))
      (node (ref "C31") (pin "P$2") (pinfunction "2_P$2") (pintype "passive"))
      (node (ref "L1") (pin "P$2") (pinfunction "2_P$2") (pintype "passive"))
      (node (ref "U2") (pin "13") (pinfunction "VDDA_13") (pintype "power_in"))
    )
    (net (code "43") (name "Net-(C35-1)") (class "Default")
      (node (ref "C35") (pin "P$1") (pinfunction "1_P$1") (pintype "passive"))
      (node (ref "VREG1") (pin "4") (pinfunction "BYP_4") (pintype "bidirectional"))
    )
    (net (code "44") (name "Net-(C42-2)") (class "Default")
      (node (ref "C42") (pin "P$2") (pinfunction "2_P$2") (pintype "passive"))
      (node (ref "R58") (pin "P$2") (pinfunction "2_P$2") (pintype "passive"))
      (node (ref "R59") (pin "P$1") (pinfunction "1_P$1") (pintype "passive"))
      (node (ref "R60") (pin "P$2") (pinfunction "2_P$2") (pintype "passive"))
      (node (ref "R61") (pin "P$1") (pinfunction "1_P$1") (pintype "passive"))
    )
    (net (code "45") (name "Net-(R8-1)") (class "Default")
      (node (ref "LED2") (pin "A") (pinfunction "A_A") (pintype "passive"))
      (node (ref "R8") (pin "P$1") (pinfunction "1_P$1") (pintype "passive"))
    )
    (net (code "46") (name "Net-(R9-1)") (class "Default")
      (node (ref "J1") (pin "2") (pinfunction "2_2") (pintype "bidirectional"))
      (node (ref "R9") (pin "P$1") (pinfunction "1_P$1") (pintype "passive"))
    )
    (net (code "47") (name "Net-(R10-1)") (class "Default")
      (node (ref "LED1") (pin "A") (pinfunction "A_A") (pintype "passive"))
      (node (ref "R10") (pin "P$1") (pinfunction "1_P$1") (pintype "passive"))
    )
    (net (code "48") (name "Net-(R11-1)") (class "Default")
      (node (ref "J2") (pin "2") (pinfunction "2_2") (pintype "bidirectional"))
      (node (ref "R11") (pin "P$1") (pinfunction "1_P$1") (pintype "passive"))
    )
    (net (code "49") (name "Net-(R12-1)") (class "Default")
      (node (ref "LED5") (pin "A") (pinfunction "A_A") (pintype "passive"))
      (node (ref "R12") (pin "P$1") (pinfunction "1_P$1") (pintype "passive"))
    )
    (net (code "50") (name "Net-(R13-1)") (class "Default")
      (node (ref "J4") (pin "2") (pinfunction "2_2") (pintype "bidirectional"))
      (node (ref "R13") (pin "P$1") (pinfunction "1_P$1") (pintype "passive"))
    )
    (net (code "51") (name "Net-(R14-1)") (class "Default")
      (node (ref "J5") (pin "2") (pinfunction "2_2") (pintype "bidirectional"))
      (node (ref "R14") (pin "P$1") (pinfunction "1_P$1") (pintype "passive"))
    )
    (net (code "52") (name "Net-(R15-1)") (class "Default")
      (node (ref "J6") (pin "2") (pinfunction "2_2") (pintype "bidirectional"))
      (node (ref "R15") (pin "P$1") (pinfunction "1_P$1") (pintype "passive"))
    )
    (net (code "53") (name "Net-(R16-1)") (class "Default")
      (node (ref "J7") (pin "2") (pinfunction "2_2") (pintype "bidirectional"))
      (node (ref "R16") (pin "P$1") (pinfunction "1_P$1") (pintype "passive"))
    )
    (net (code "54") (name "Net-(R19-1)") (class "Default")
      (node (ref "J8") (pin "2") (pinfunction "2_2") (pintype "bidirectional"))
      (node (ref "R19") (pin "P$1") (pinfunction "1_P$1") (pintype "passive"))
    )
    (net (code "55") (name "Net-(R20-1)") (class "Default")
      (node (ref "J3") (pin "2") (pinfunction "2_2") (pintype "bidirectional"))
      (node (ref "R20") (pin "P$1") (pinfunction "1_P$1") (pintype "passive"))
    )
    (net (code "56") (name "Net-(R23-1)") (class "Default")
      (node (ref "LEDVIN") (pin "A") (pinfunction "A_A") (pintype "passive"))
      (node (ref "R23") (pin "P$1") (pinfunction "1_P$1") (pintype "passive"))
    )
    (net (code "57") (name "Net-(R32-1)") (class "Default")
      (node (ref "LED6") (pin "A") (pinfunction "A_A") (pintype "passive"))
      (node (ref "R32") (pin "P$1") (pinfunction "1_P$1") (pintype "passive"))
    )
    (net (code "58") (name "Net-(R35-1)") (class "Default")
      (node (ref "LED7") (pin "A") (pinfunction "A_A") (pintype "passive"))
      (node (ref "R35") (pin "P$1") (pinfunction "1_P$1") (pintype "passive"))
    )
    (net (code "59") (name "Net-(R36-1)") (class "Default")
      (node (ref "LED8") (pin "A") (pinfunction "A_A") (pintype "passive"))
      (node (ref "R36") (pin "P$1") (pinfunction "1_P$1") (pintype "passive"))
    )
    (net (code "60") (name "Net-(R37-1)") (class "Default")
      (node (ref "LED4") (pin "A") (pinfunction "A_A") (pintype "passive"))
      (node (ref "R37") (pin "P$1") (pinfunction "1_P$1") (pintype "passive"))
    )
    (net (code "61") (name "Net-(R38-1)") (class "Default")
      (node (ref "LED3") (pin "A") (pinfunction "A_A") (pintype "passive"))
      (node (ref "R38") (pin "P$1") (pinfunction "1_P$1") (pintype "passive"))
    )
    (net (code "62") (name "Net-(R55-2)") (class "Default")
      (node (ref "R55") (pin "P$2") (pinfunction "2_P$2") (pintype "passive"))
      (node (ref "R56") (pin "P$1") (pinfunction "1_P$1") (pintype "passive"))
      (node (ref "U1") (pin "8") (pinfunction "RS_8") (pintype "input"))
    )
    (net (code "63") (name "OSC_IN") (class "Default")
      (node (ref "C4") (pin "P$2") (pinfunction "2_P$2") (pintype "passive"))
      (node (ref "Q1") (pin "P$3") (pinfunction "P$3_P$3") (pintype "bidirectional"))
      (node (ref "U2") (pin "5") (pinfunction "PD0-OSC_IN-CAN1RX_5") (pintype "input"))
    )
    (net (code "64") (name "OSC_OUT") (class "Default")
      (node (ref "C6") (pin "P$1") (pinfunction "1_P$1") (pintype "passive"))
      (node (ref "Q1") (pin "P$1") (pinfunction "P$1_P$1") (pintype "bidirectional"))
      (node (ref "U2") (pin "6") (pinfunction "PD1-OSC_OUT-CAN1TX_6") (pintype "output"))
    )
    (net (code "65") (name "PC12") (class "Default")
      (node (ref "JP15") (pin "3") (pinfunction "3_3") (pintype "passive"))
      (node (ref "U2") (pin "53") (pinfunction "PC12-USART5TX-USART3CK/SPI3MOSI/I2S3SD_53") (pintype "bidirectional"))
    )
    (net (code "66") (name "S1") (class "Default")
      (node (ref "J1") (pin "3") (pinfunction "3_3") (pintype "bidirectional"))
      (node (ref "R41") (pin "P$1") (pinfunction "1_P$1") (pintype "passive"))
    )
    (net (code "67") (name "S2") (class "Default")
      (node (ref "J2") (pin "3") (pinfunction "3_3") (pintype "bidirectional"))
      (node (ref "R42") (pin "P$1") (pinfunction "1_P$1") (pintype "passive"))
    )
    (net (code "68") (name "S3") (class "Default")
      (node (ref "J3") (pin "3") (pinfunction "3_3") (pintype "bidirectional"))
      (node (ref "R45") (pin "P$1") (pinfunction "1_P$1") (pintype "passive"))
    )
    (net (code "69") (name "S4") (class "Default")
      (node (ref "J4") (pin "3") (pinfunction "3_3") (pintype "bidirectional"))
      (node (ref "R27") (pin "P$1") (pinfunction "1_P$1") (pintype "passive"))
    )
    (net (code "70") (name "S5") (class "Default")
      (node (ref "J5") (pin "3") (pinfunction "3_3") (pintype "bidirectional"))
      (node (ref "R28") (pin "P$1") (pinfunction "1_P$1") (pintype "passive"))
    )
    (net (code "71") (name "S6") (class "Default")
      (node (ref "J6") (pin "3") (pinfunction "3_3") (pintype "bidirectional"))
      (node (ref "R31") (pin "P$1") (pinfunction "1_P$1") (pintype "passive"))
    )
    (net (code "72") (name "S7") (class "Default")
      (node (ref "J7") (pin "3") (pinfunction "3_3") (pintype "bidirectional"))
      (node (ref "R39") (pin "P$1") (pinfunction "1_P$1") (pintype "passive"))
    )
    (net (code "73") (name "S8") (class "Default")
      (node (ref "J8") (pin "3") (pinfunction "3_3") (pintype "bidirectional"))
      (node (ref "R40") (pin "P$1") (pinfunction "1_P$1") (pintype "passive"))
    )
    (net (code "74") (name "SERVO_1") (class "Default")
      (node (ref "R41") (pin "P$2") (pinfunction "2_P$2") (pintype "passive"))
      (node (ref "U2") (pin "37") (pinfunction "PC6-I2S2MCK-TIM3CH1_37") (pintype "bidirectional"))
    )
    (net (code "75") (name "SERVO_2") (class "Default")
      (node (ref "R42") (pin "P$2") (pinfunction "2_P$2") (pintype "passive"))
      (node (ref "U2") (pin "38") (pinfunction "PC7-I2S3MCK-TIM3CH2_38") (pintype "bidirectional"))
    )
    (net (code "76") (name "SERVO_3") (class "Default")
      (node (ref "R45") (pin "P$2") (pinfunction "2_P$2") (pintype "passive"))
      (node (ref "U2") (pin "39") (pinfunction "PC8-TIM3CH3_39") (pintype "bidirectional"))
    )
    (net (code "77") (name "SERVO_4") (class "Default")
      (node (ref "R27") (pin "P$2") (pinfunction "2_P$2") (pintype "passive"))
      (node (ref "U2") (pin "40") (pinfunction "PC9-TIM3CH4_40") (pintype "bidirectional"))
    )
    (net (code "78") (name "SERVO_5") (class "Default")
      (node (ref "R28") (pin "P$2") (pinfunction "2_P$2") (pintype "passive"))
      (node (ref "U2") (pin "14") (pinfunction "PA0-WKUP/USART2CTS/ADC0/TIM2CH1ETR/TIM5CH1/ETH_MII_CRS_WKUP_14") (pintype "bidirectional"))
    )
    (net (code "79") (name "SERVO_6") (class "Default")
      (node (ref "R31") (pin "P$2") (pinfunction "2_P$2") (pintype "passive"))
      (node (ref "U2") (pin "15") (pinfunction "PA1-USART2RTS/ADC1/TIM5CH2/TIM2CH2/ETH_MII_RX_CLK/ETH_RMII_REF_CLK_15") (pintype "bidirectional"))
    )
    (net (code "80") (name "SERVO_7{slash}I2C1_SCL") (class "Default")
      (node (ref "JP10") (pin "P$1") (pinfunction "1_P$1") (pintype "passive"))
      (node (ref "LT_I2C2") (pin "3") (pinfunction "SCL1_3") (pintype "bidirectional"))
      (node (ref "R33") (pin "P$1") (pinfunction "1_P$1") (pintype "passive"))
      (node (ref "R39") (pin "P$2") (pinfunction "2_P$2") (pintype "passive"))
      (node (ref "U2") (pin "58") (pinfunction "PB6-I2C1SCL/TIM4CH1-USART1TX/CAN2TX_58") (pintype "bidirectional"))
    )
    (net (code "81") (name "SERVO_8{slash}I2C1_SDA") (class "Default")
      (node (ref "JP11") (pin "P$1") (pinfunction "1_P$1") (pintype "passive"))
      (node (ref "LT_I2C2") (pin "4") (pinfunction "SDA1_4") (pintype "bidirectional"))
      (node (ref "R34") (pin "P$1") (pinfunction "1_P$1") (pintype "passive"))
      (node (ref "R40") (pin "P$2") (pinfunction "2_P$2") (pintype "passive"))
      (node (ref "U2") (pin "59") (pinfunction "PB7-I2C1SDA/TIM4CH2-USART1RX_59") (pintype "bidirectional"))
    )
    (net (code "82") (name "SERVO_BUS") (class "Default")
      (node (ref "JP1") (pin "P$1") (pinfunction "1_P$1") (pintype "passive"))
      (node (ref "R11") (pin "P$2") (pinfunction "2_P$2") (pintype "passive"))
      (node (ref "R13") (pin "P$2") (pinfunction "2_P$2") (pintype "passive"))
      (node (ref "R14") (pin "P$2") (pinfunction "2_P$2") (pintype "passive"))
      (node (ref "R15") (pin "P$2") (pinfunction "2_P$2") (pintype "passive"))
      (node (ref "R16") (pin "P$2") (pinfunction "2_P$2") (pintype "passive"))
      (node (ref "R19") (pin "P$2") (pinfunction "2_P$2") (pintype "passive"))
      (node (ref "R20") (pin "P$2") (pinfunction "2_P$2") (pintype "passive"))
      (node (ref "R9") (pin "P$2") (pinfunction "2_P$2") (pintype "passive"))
    )
    (net (code "83") (name "U1_U5_POW") (class "Default")
      (node (ref "JP20") (pin "2") (pinfunction "2_2") (pintype "passive"))
      (node (ref "JP20") (pin "5") (pinfunction "5_5") (pintype "passive"))
      (node (ref "JP8") (pin "P$2") (pinfunction "2_P$2") (pintype "passive"))
      (node (ref "JP9") (pin "P$2") (pinfunction "2_P$2") (pintype "passive"))
      (node (ref "R24") (pin "P$1") (pinfunction "1_P$1") (pintype "passive"))
      (node (ref "R6") (pin "P$1") (pinfunction "1_P$1") (pintype "passive"))
    )
    (net (code "84") (name "U2_POW") (class "Default")
      (node (ref "JP16") (pin "2") (pinfunction "2_2") (pintype "passive"))
      (node (ref "JP4") (pin "P$2") (pinfunction "2_P$2") (pintype "passive"))
      (node (ref "JP5") (pin "P$2") (pinfunction "2_P$2") (pintype "passive"))
      (node (ref "R26") (pin "P$1") (pinfunction "1_P$1") (pintype "passive"))
    )
    (net (code "85") (name "U3_POW") (class "Default")
      (node (ref "JP17") (pin "2") (pinfunction "2_2") (pintype "passive"))
      (node (ref "JP6") (pin "P$2") (pinfunction "2_P$2") (pintype "passive"))
      (node (ref "JP7") (pin "P$2") (pinfunction "2_P$2") (pintype "passive"))
      (node (ref "R3") (pin "P$1") (pinfunction "1_P$1") (pintype "passive"))
    )
    (net (code "86") (name "UART1_RX") (class "Default")
      (node (ref "JP20") (pin "3") (pinfunction "3_3") (pintype "passive"))
      (node (ref "R24") (pin "P$2") (pinfunction "2_P$2") (pintype "passive"))
      (node (ref "U2") (pin "43") (pinfunction "PA10-USART1RX/TIM1CH3/OTG_FS_ID_43") (pintype "bidirectional"))
    )
    (net (code "87") (name "UART2_RX") (class "Default")
      (node (ref "JP16") (pin "4") (pinfunction "4_4") (pintype "passive"))
      (node (ref "R26") (pin "P$2") (pinfunction "2_P$2") (pintype "passive"))
      (node (ref "U2") (pin "17") (pinfunction "PA3-USART2RX/TIM5CH4/ADC3/TIM2CH4/ETH_MII_COL_17") (pintype "bidirectional"))
    )
    (net (code "88") (name "UART2_TX") (class "Default")
      (node (ref "JP16") (pin "3") (pinfunction "3_3") (pintype "passive"))
      (node (ref "U2") (pin "16") (pinfunction "PA2-USART2TX/TIM5CH3/ADC2/TIM2CH3/ETH_(R)MII_MDIO_16") (pintype "bidirectional"))
    )
    (net (code "89") (name "UART3_RX") (class "Default")
      (node (ref "JP17") (pin "4") (pinfunction "4_4") (pintype "passive"))
      (node (ref "R3") (pin "P$2") (pinfunction "2_P$2") (pintype "passive"))
      (node (ref "U2") (pin "52") (pinfunction "PC11-USART4RX-USART3RX/SPI3MISO_52") (pintype "bidirectional"))
    )
    (net (code "90") (name "UART3_TX") (class "Default")
      (node (ref "JP17") (pin "3") (pinfunction "3_3") (pintype "passive"))
      (node (ref "U2") (pin "51") (pinfunction "PC10-USART4TX-USART3TX/SPI3SCK/I2S3CK_51") (pintype "bidirectional"))
    )
    (net (code "91") (name "UART5_RX") (class "Default")
      (node (ref "JP20") (pin "6") (pinfunction "6_6") (pintype "passive"))
      (node (ref "R6") (pin "P$2") (pinfunction "2_P$2") (pintype "passive"))
      (node (ref "U2") (pin "54") (pinfunction "PD2-TIM3ETR/USART5RX_54") (pintype "bidirectional"))
    )
    (net (code "92") (name "USB_DM") (class "Default")
      (node (ref "CON_USB_MICRO") (pin "PIN_2") (pinfunction "2_PIN_2") (pintype "input"))
      (node (ref "U2") (pin "44") (pinfunction "PA11-USART1CTS/CAN1RX/OTG_FS_DM/TIM1CH4_44") (pintype "bidirectional"))
    )
    (net (code "93") (name "USB_DP") (class "Default")
      (node (ref "CON_USB_MICRO") (pin "PIN_3") (pinfunction "3_PIN_3") (pintype "input"))
      (node (ref "U2") (pin "45") (pinfunction "PA12-USART1RTS/CAN1TX/OTG_FS_DP/TIM1ETR_45") (pintype "bidirectional"))
    )
    (net (code "94") (name "USB_VBUS") (class "Default")
      (node (ref "CON_USB_MICRO") (pin "PIN_1") (pinfunction "1_PIN_1") (pintype "input"))
      (node (ref "D3") (pin "A") (pinfunction "A_A") (pintype "passive"))
      (node (ref "U2") (pin "42") (pinfunction "PA9-USART1TX/TIM1CH2/OTG_FS_VBUS_42") (pintype "bidirectional"))
    )
    (net (code "95") (name "VREF") (class "Default")
      (node (ref "U1") (pin "5") (pinfunction "VREF_5") (pintype "power_in"))
    )
    (net (code "96") (name "VSS1") (class "Default")
      (node (ref "C7") (pin "P$2") (pinfunction "2_P$2") (pintype "passive"))
      (node (ref "JP12") (pin "P$1") (pinfunction "1_P$1") (pintype "passive"))
      (node (ref "U2") (pin "31") (pinfunction "VSS1_31") (pintype "power_in"))
    )
    (net (code "97") (name "VSS2") (class "Default")
      (node (ref "C14") (pin "P$2") (pinfunction "2_P$2") (pintype "passive"))
      (node (ref "JP13") (pin "P$1") (pinfunction "1_P$1") (pintype "passive"))
      (node (ref "U2") (pin "47") (pinfunction "VSS2_47") (pintype "power_in"))
    )
    (net (code "98") (name "V_BAT") (class "Default")
      (node (ref "JP2") (pin "P$2") (pinfunction "2_P$2") (pintype "passive"))
      (node (ref "JP21") (pin "2") (pinfunction "2_2") (pintype "passive"))
      (node (ref "R17") (pin "P$1") (pinfunction "1_P$1") (pintype "passive"))
    )
    (net (code "99") (name "V_BAT_MEAS") (class "Default")
      (node (ref "R17") (pin "P$2") (pinfunction "2_P$2") (pintype "passive"))
      (node (ref "R18") (pin "P$1") (pinfunction "1_P$1") (pintype "passive"))
      (node (ref "U2") (pin "24") (pinfunction "PC4-ADC14/ETH_(R)MII_RXD0_24") (pintype "bidirectional"))
    )
    (net (code "100") (name "V_IN") (class "Default")
      (node (ref "C3") (pin "P$1") (pinfunction "1_P$1") (pintype "passive"))
      (node (ref "C38") (pin "P$1") (pinfunction "1_P$1") (pintype "passive"))
      (node (ref "C39") (pin "+") (pinfunction "+_+") (pintype "passive"))
      (node (ref "D3") (pin "C") (pinfunction "C_C") (pintype "passive"))
      (node (ref "IC9") (pin "1") (pinfunction "VIN_1") (pintype "bidirectional"))
      (node (ref "IC9") (pin "3") (pinfunction "ON/OFF_3") (pintype "bidirectional"))
      (node (ref "IMU") (pin "P$2") (pinfunction "VCC_P$2") (pintype "bidirectional"))
      (node (ref "JP1") (pin "P$2") (pinfunction "2_P$2") (pintype "passive"))
      (node (ref "JP2") (pin "P$1") (pinfunction "1_P$1") (pintype "passive"))
      (node (ref "JP21") (pin "3") (pinfunction "3_3") (pintype "passive"))
      (node (ref "JP3") (pin "P$1") (pinfunction "1_P$1") (pintype "passive"))
      (node (ref "JP4") (pin "P$1") (pinfunction "1_P$1") (pintype "passive"))
      (node (ref "JP6") (pin "P$1") (pinfunction "1_P$1") (pintype "passive"))
      (node (ref "JP8") (pin "P$1") (pinfunction "1_P$1") (pintype "passive"))
      (node (ref "R23") (pin "P$2") (pinfunction "2_P$2") (pintype "passive"))
      (node (ref "VREG1") (pin "1") (pinfunction "ENABLE_1") (pintype "bidirectional"))
      (node (ref "VREG1") (pin "2") (pinfunction "VIN_2") (pintype "bidirectional"))
    )
    (net (code "101") (name "unconnected-(CON_USB_MICRO-4-PadPIN_4)") (class "Default")
      (node (ref "CON_USB_MICRO") (pin "PIN_4") (pinfunction "4_PIN_4") (pintype "input"))
    )
  )
)
